# throughhole_xbee.net
KiCad netlist of a schematic drawn in EAGLE
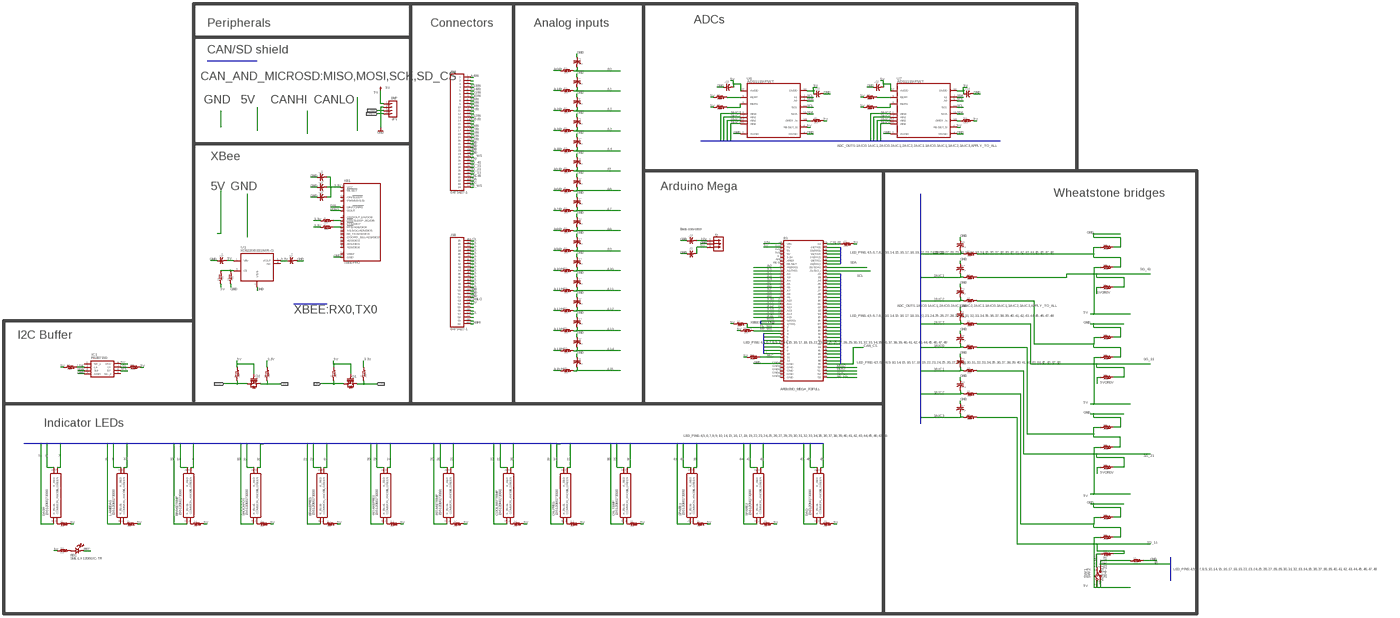
[diagram p0: schematic, sheet 1, overview]
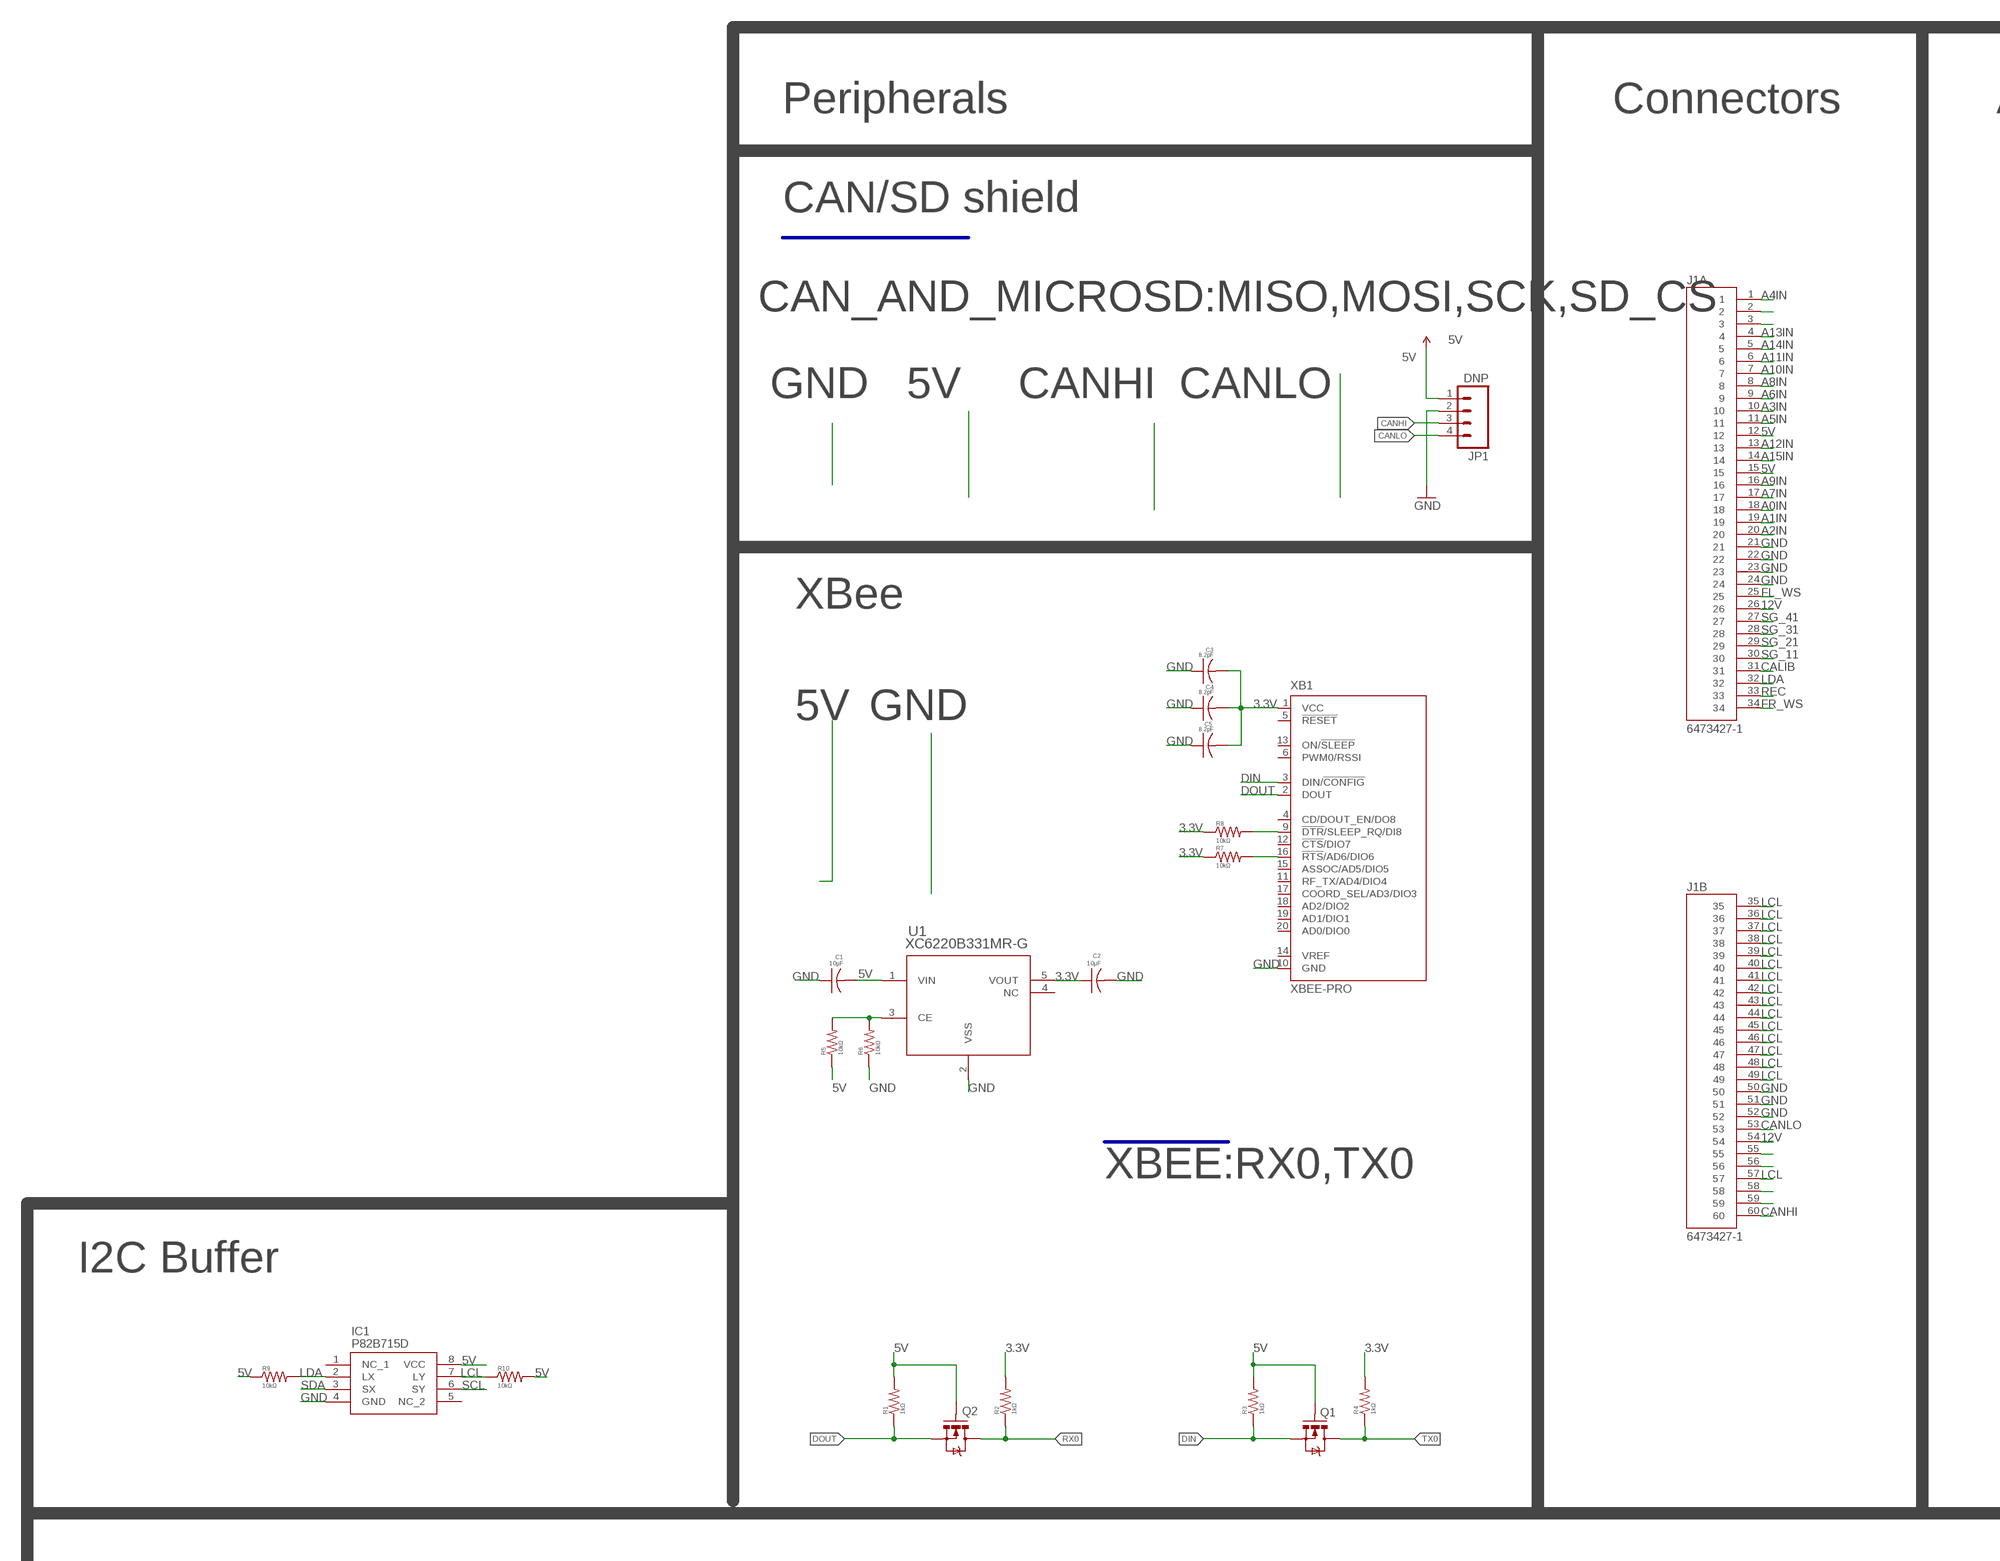
[diagram p1: schematic, sheet 1, part 1 of 5]
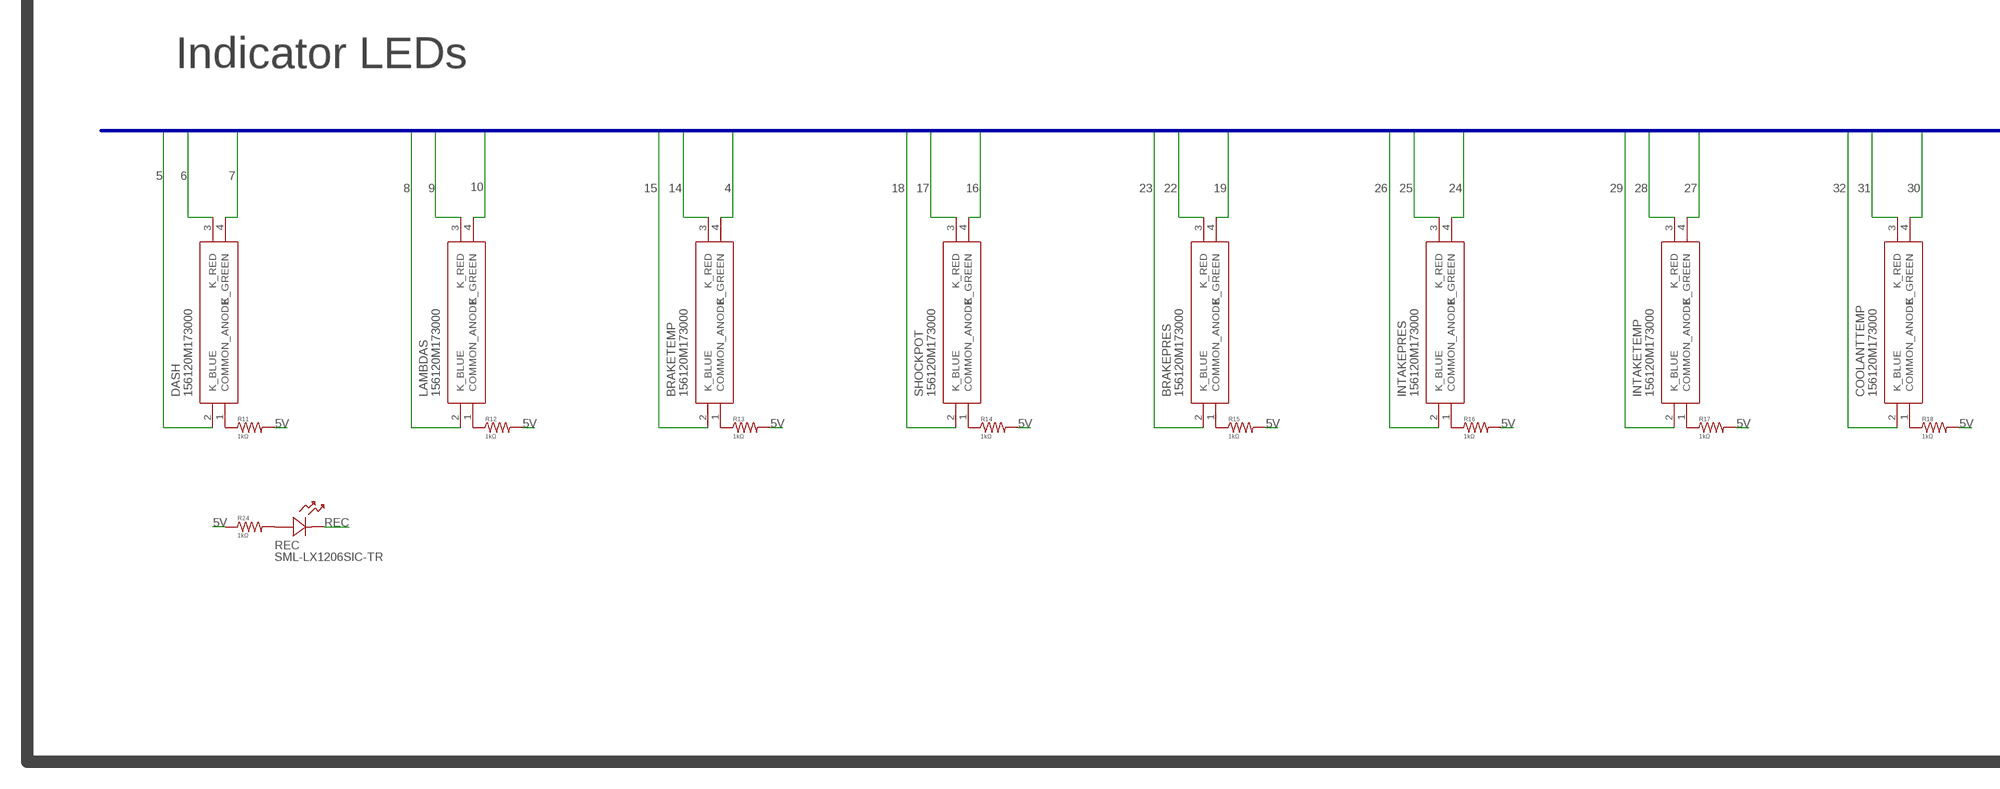
[diagram p2: schematic, sheet 1, part 2 of 5]
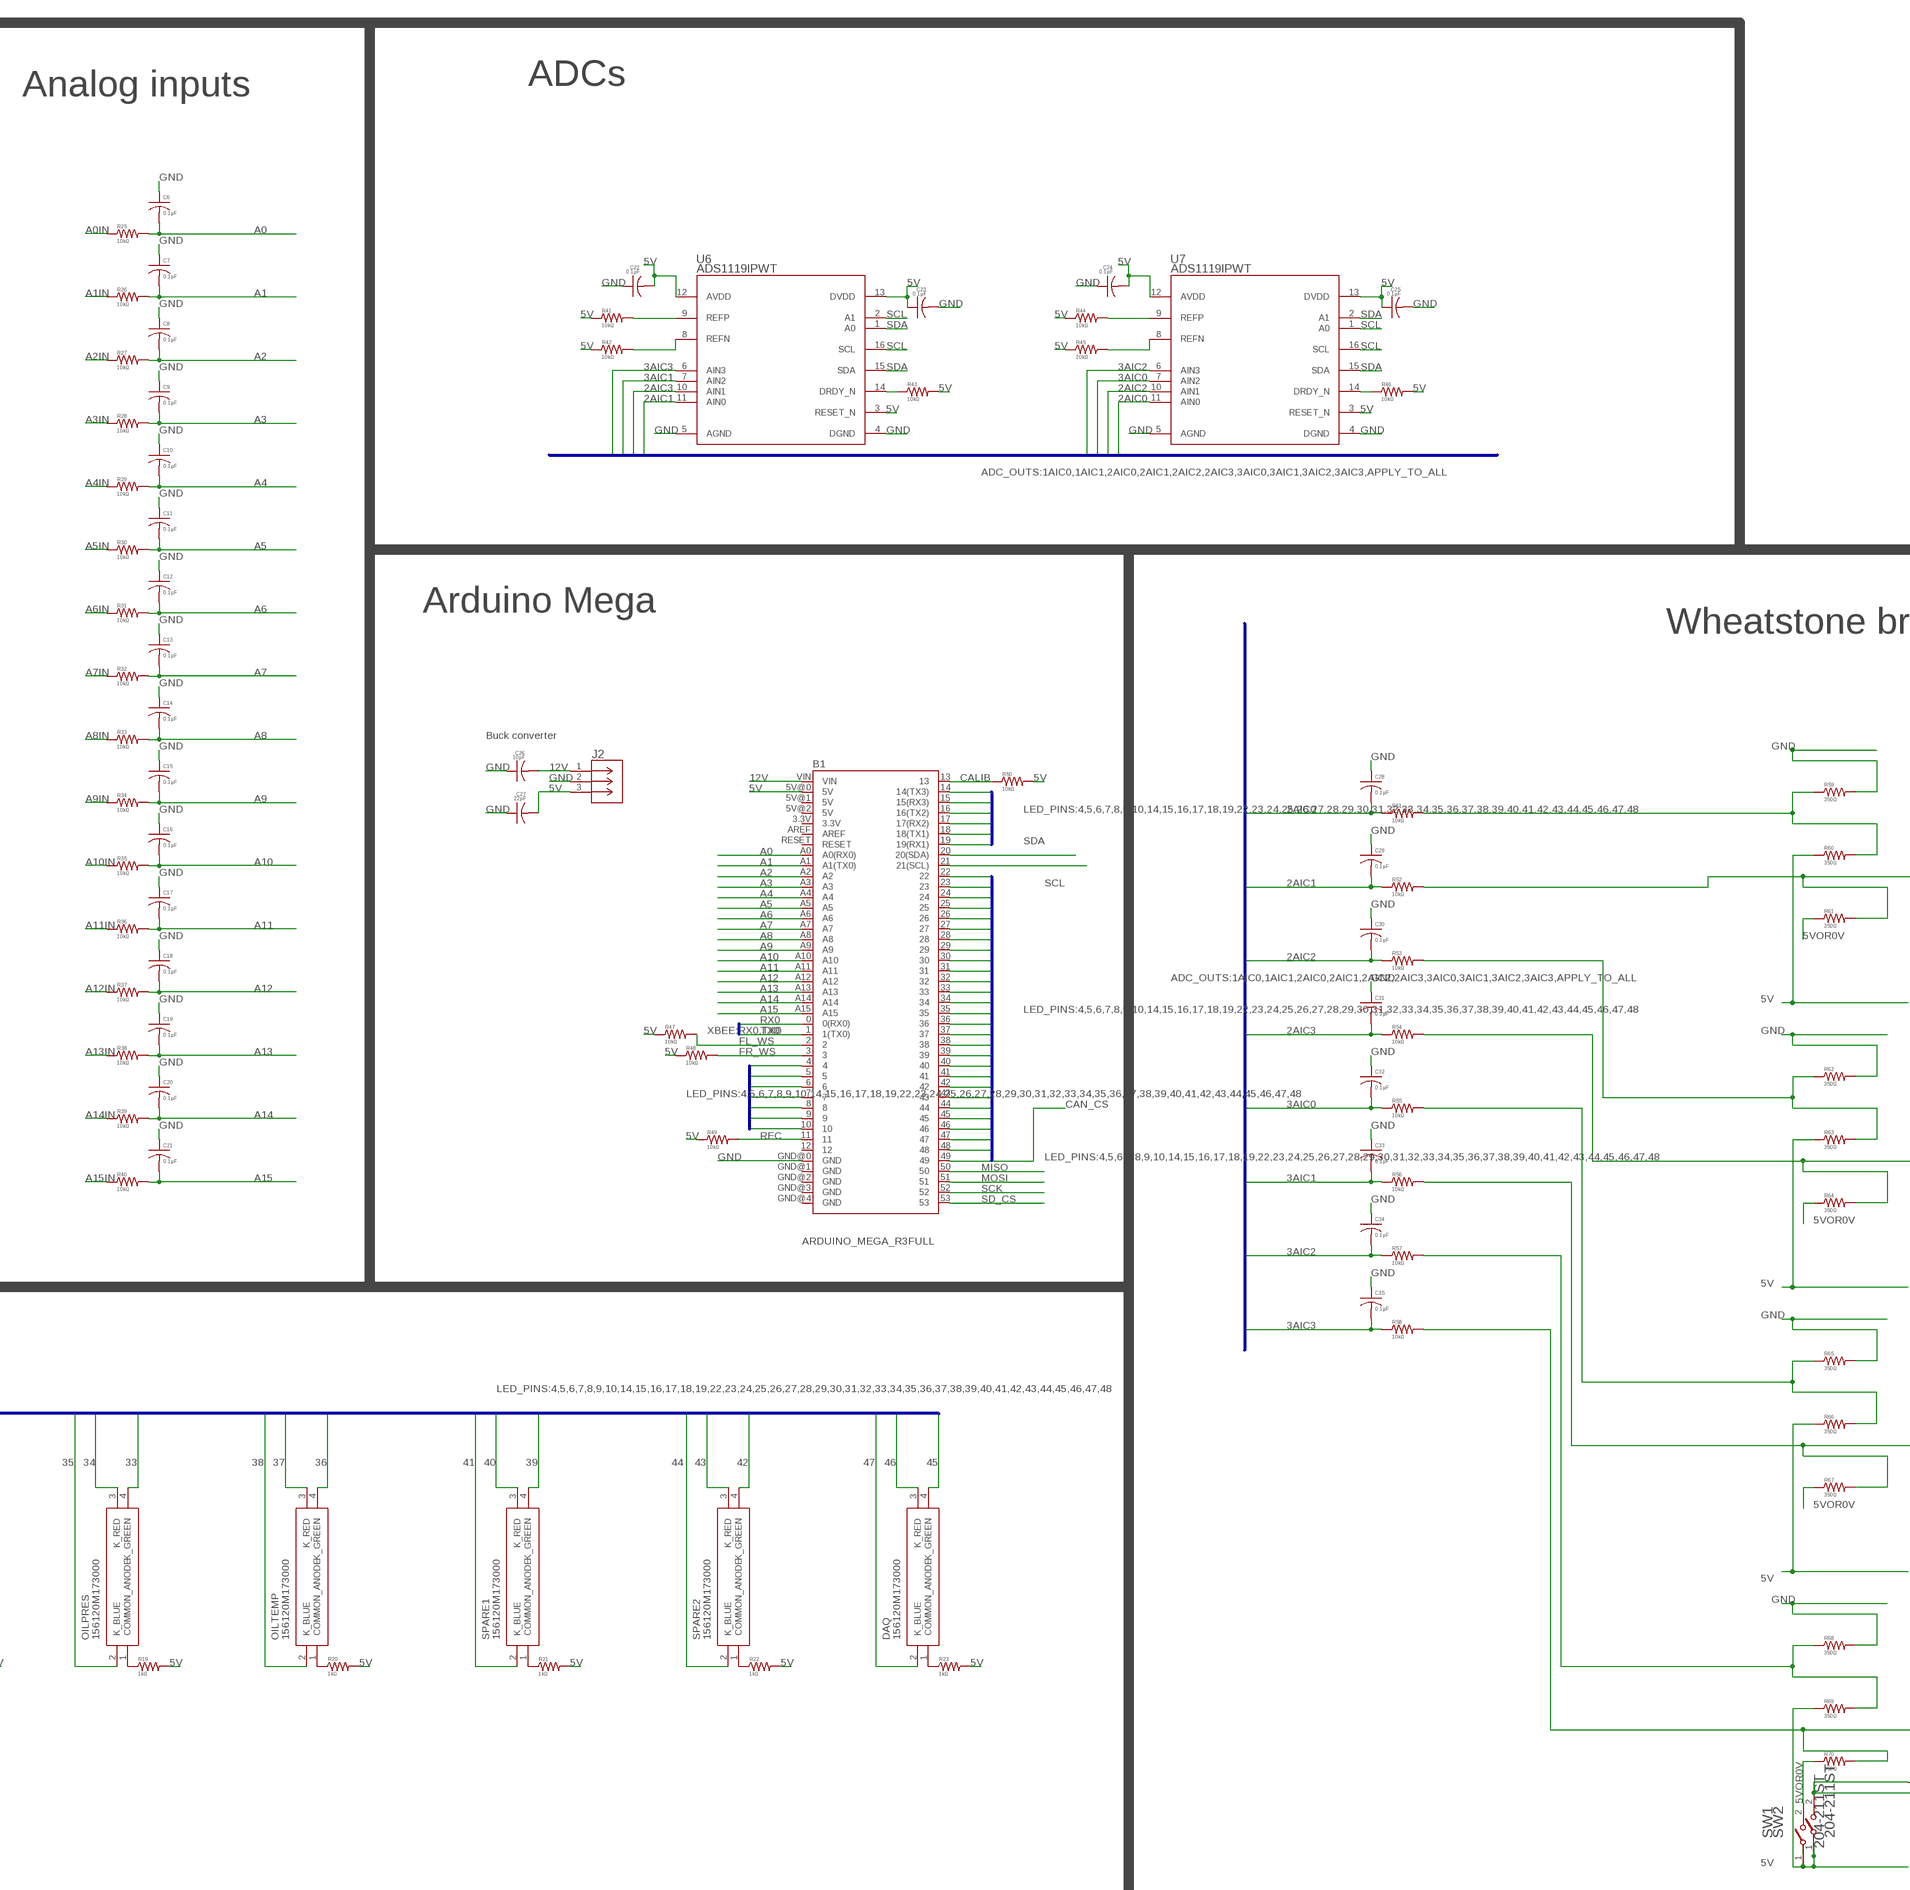
[diagram p3: schematic, sheet 1, part 3 of 5]
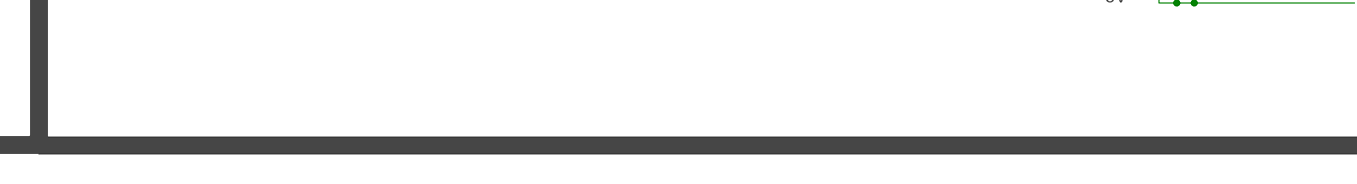
[diagram p4: schematic, sheet 1, part 4 of 5]
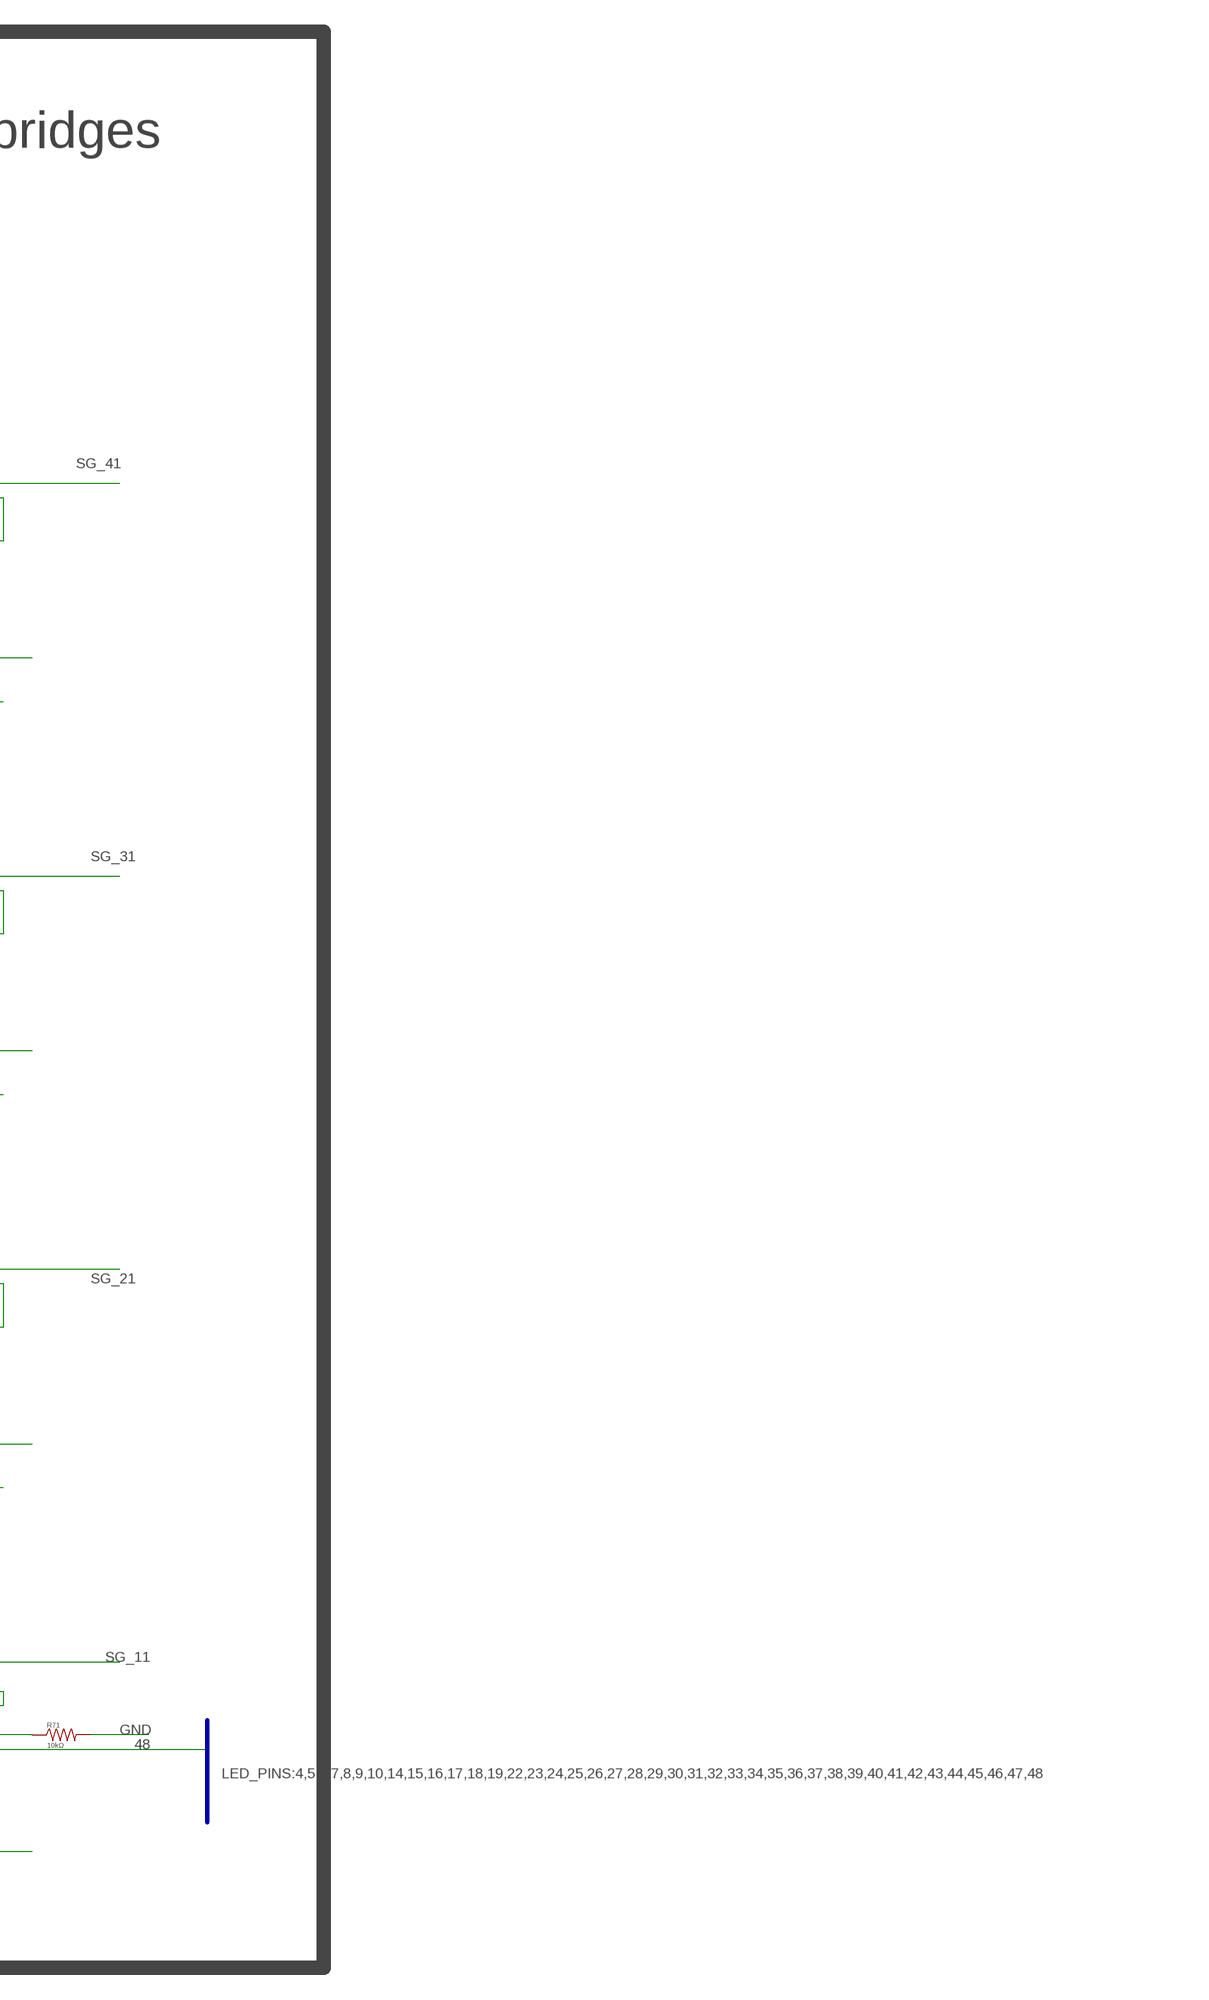
[diagram p5: schematic, sheet 1, part 5 of 5]
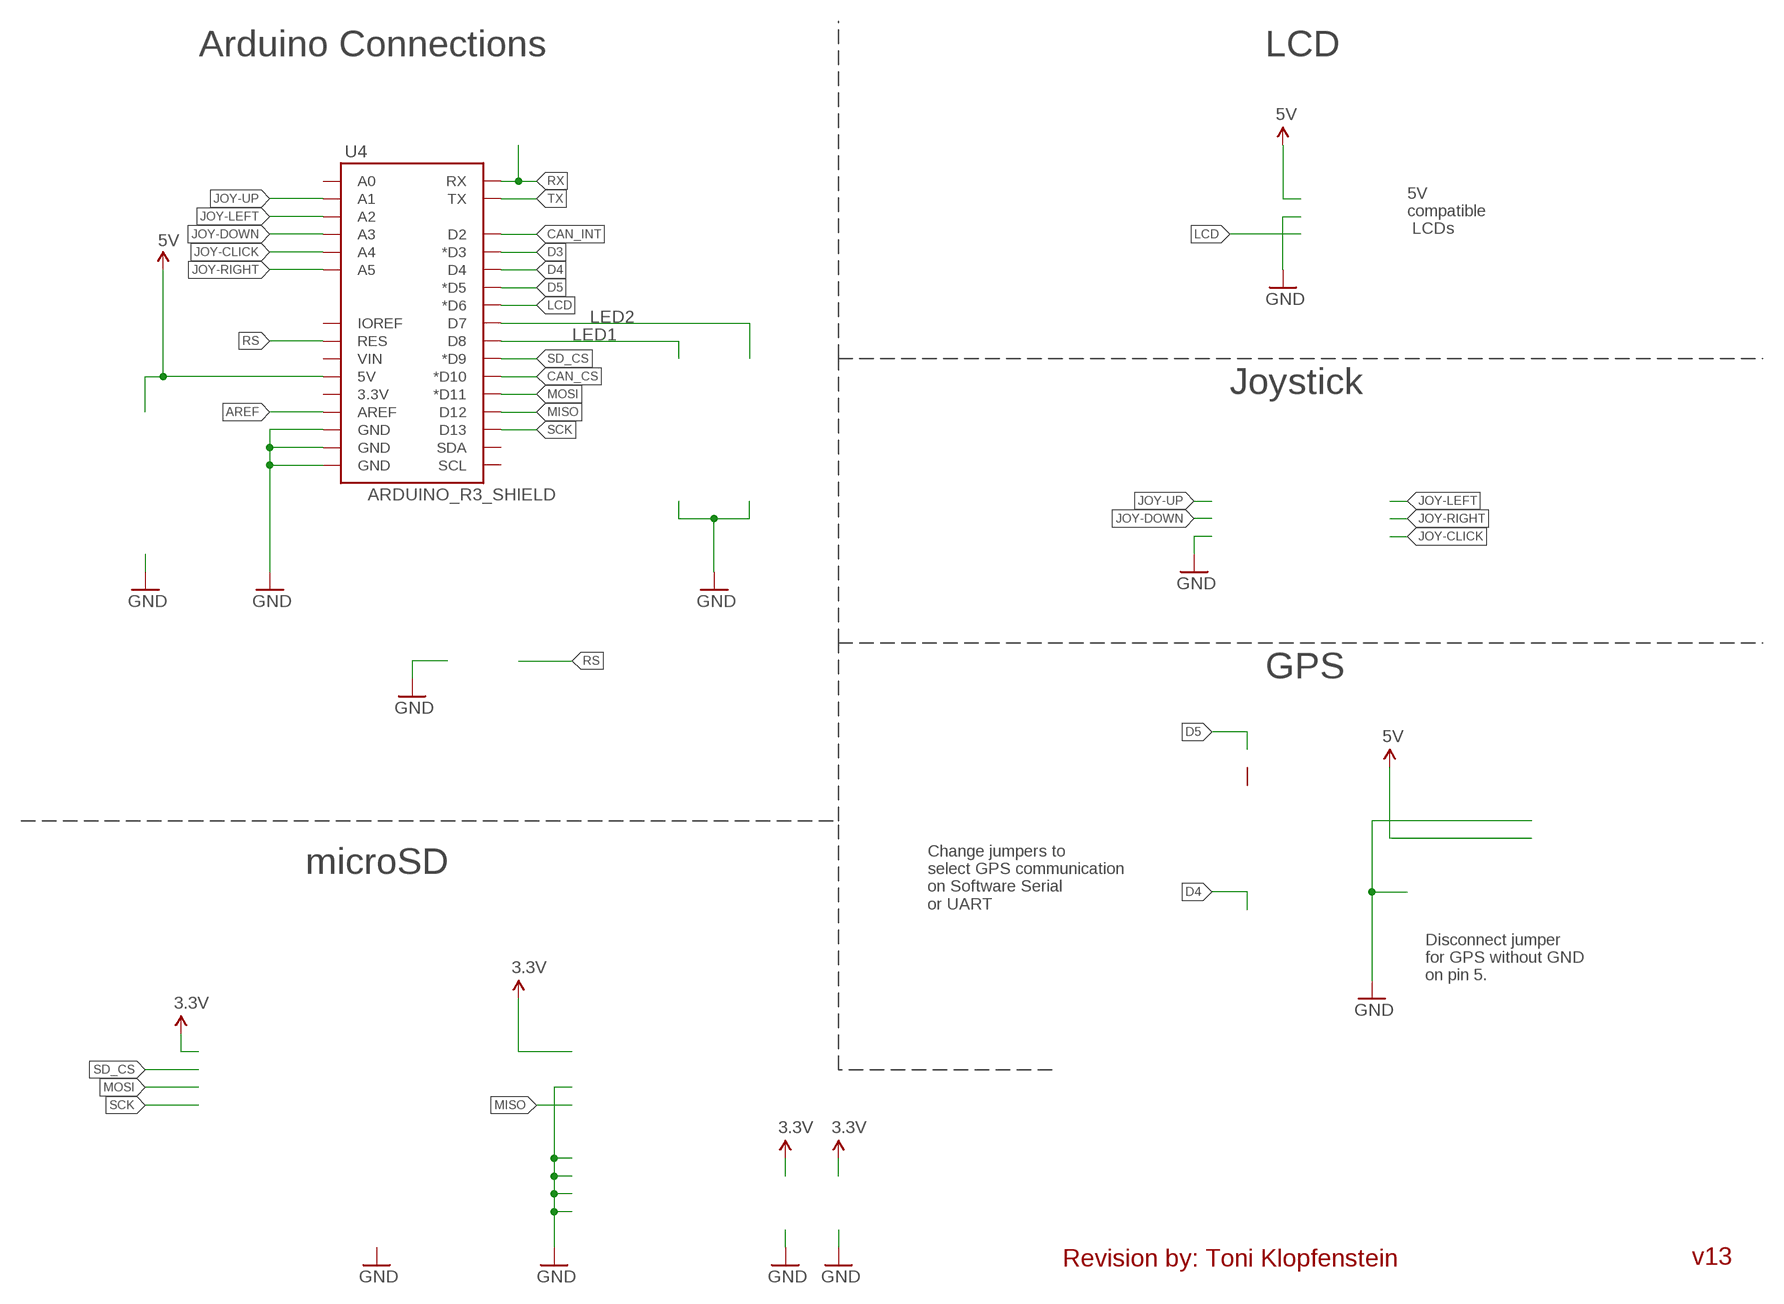
[diagram p6: schematic, sheet 2]

(export (version "E")
  (design (tool "Eeschema 10.0.6"))
  (components
    (comp (ref "B1")
      (value "ARDUINO_MEGA_R3FULL")
      (footprint "eagle-import:ARDUINO_MEGA")
      (libsource (lib "eagle-import") (part "ARDUINO_MEGA_R3FULL"))
    )
    (comp (ref "BRAKEPRES")
      (value "156120M173000")
      (footprint "eagle-import:156120M173000")
      (fields (field (name "MOUSER_PART_NUMBER") "710-156120M173000"))
      (libsource (lib "eagle-import") (part "156120M173000"))
    )
    (comp (ref "BRAKETEMP")
      (value "156120M173000")
      (footprint "eagle-import:156120M173000")
      (fields (field (name "MOUSER_PART_NUMBER") "710-156120M173000"))
      (libsource (lib "eagle-import") (part "156120M173000"))
    )
    (comp (ref "C1")
      (value "10μF")
      (footprint "eagle-import:C1206")
      (libsource (lib "eagle-import") (part "C-USC1206"))
    )
    (comp (ref "C2")
      (value "10μF")
      (footprint "eagle-import:C1206")
      (libsource (lib "eagle-import") (part "C-USC1206"))
    )
    (comp (ref "C3")
      (value "8.2pF")
      (footprint "eagle-import:C1206")
      (libsource (lib "eagle-import") (part "C-USC1206"))
    )
    (comp (ref "C4")
      (value "8.2pF")
      (footprint "eagle-import:C1206")
      (libsource (lib "eagle-import") (part "C-USC1206"))
    )
    (comp (ref "C5")
      (value "8.2pF")
      (footprint "eagle-import:C1206")
      (libsource (lib "eagle-import") (part "C-USC1206"))
    )
    (comp (ref "C6")
      (value "0.1μF")
      (footprint "eagle-import:C1206")
      (libsource (lib "eagle-import") (part "C-USC1206"))
    )
    (comp (ref "C7")
      (value "0.1μF")
      (footprint "eagle-import:C1206")
      (libsource (lib "eagle-import") (part "C-USC1206"))
    )
    (comp (ref "C8")
      (value "0.1μF")
      (footprint "eagle-import:C1206")
      (libsource (lib "eagle-import") (part "C-USC1206"))
    )
    (comp (ref "C9")
      (value "0.1μF")
      (footprint "eagle-import:C1206")
      (libsource (lib "eagle-import") (part "C-USC1206"))
    )
    (comp (ref "C10")
      (value "0.1μF")
      (footprint "eagle-import:C1206")
      (libsource (lib "eagle-import") (part "C-USC1206"))
    )
    (comp (ref "C11")
      (value "0.1μF")
      (footprint "eagle-import:C1206")
      (libsource (lib "eagle-import") (part "C-USC1206"))
    )
    (comp (ref "C12")
      (value "0.1μF")
      (footprint "eagle-import:C1206")
      (libsource (lib "eagle-import") (part "C-USC1206"))
    )
    (comp (ref "C13")
      (value "0.1μF")
      (footprint "eagle-import:C1206")
      (libsource (lib "eagle-import") (part "C-USC1206"))
    )
    (comp (ref "C14")
      (value "0.1μF")
      (footprint "eagle-import:C1206")
      (libsource (lib "eagle-import") (part "C-USC1206"))
    )
    (comp (ref "C15")
      (value "0.1μF")
      (footprint "eagle-import:C1206")
      (libsource (lib "eagle-import") (part "C-USC1206"))
    )
    (comp (ref "C16")
      (value "0.1μF")
      (footprint "eagle-import:C1206")
      (libsource (lib "eagle-import") (part "C-USC1206"))
    )
    (comp (ref "C17")
      (value "0.1μF")
      (footprint "eagle-import:C1206")
      (libsource (lib "eagle-import") (part "C-USC1206"))
    )
    (comp (ref "C18")
      (value "0.1μF")
      (footprint "eagle-import:C1206")
      (libsource (lib "eagle-import") (part "C-USC1206"))
    )
    (comp (ref "C19")
      (value "0.1μF")
      (footprint "eagle-import:C1206")
      (libsource (lib "eagle-import") (part "C-USC1206"))
    )
    (comp (ref "C20")
      (value "0.1μF")
      (footprint "eagle-import:C1206")
      (libsource (lib "eagle-import") (part "C-USC1206"))
    )
    (comp (ref "C21")
      (value "0.1μF")
      (footprint "eagle-import:C1206")
      (libsource (lib "eagle-import") (part "C-USC1206"))
    )
    (comp (ref "C22")
      (value "0.1μF")
      (footprint "eagle-import:C1206")
      (libsource (lib "eagle-import") (part "C-USC1206"))
    )
    (comp (ref "C23")
      (value "0.1μF")
      (footprint "eagle-import:C1206")
      (libsource (lib "eagle-import") (part "C-USC1206"))
    )
    (comp (ref "C24")
      (value "0.1μF")
      (footprint "eagle-import:C1206")
      (libsource (lib "eagle-import") (part "C-USC1206"))
    )
    (comp (ref "C25")
      (value "0.1μF")
      (footprint "eagle-import:C1206")
      (libsource (lib "eagle-import") (part "C-USC1206"))
    )
    (comp (ref "C26")
      (value "10μF")
      (footprint "eagle-import:C1206")
      (libsource (lib "eagle-import") (part "C-USC1206"))
    )
    (comp (ref "C27")
      (value "22μF")
      (footprint "eagle-import:C1206")
      (libsource (lib "eagle-import") (part "C-USC1206"))
    )
    (comp (ref "C28")
      (value "0.1μF")
      (footprint "eagle-import:C1206")
      (libsource (lib "eagle-import") (part "C-USC1206"))
    )
    (comp (ref "C29")
      (value "0.1μF")
      (footprint "eagle-import:C1206")
      (libsource (lib "eagle-import") (part "C-USC1206"))
    )
    (comp (ref "C30")
      (value "0.1μF")
      (footprint "eagle-import:C1206")
      (libsource (lib "eagle-import") (part "C-USC1206"))
    )
    (comp (ref "C31")
      (value "0.1μF")
      (footprint "eagle-import:C1206")
      (libsource (lib "eagle-import") (part "C-USC1206"))
    )
    (comp (ref "C32")
      (value "0.1μF")
      (footprint "eagle-import:C1206")
      (libsource (lib "eagle-import") (part "C-USC1206"))
    )
    (comp (ref "C33")
      (value "0.1μF")
      (footprint "eagle-import:C1206")
      (libsource (lib "eagle-import") (part "C-USC1206"))
    )
    (comp (ref "C34")
      (value "0.1μF")
      (footprint "eagle-import:C1206")
      (libsource (lib "eagle-import") (part "C-USC1206"))
    )
    (comp (ref "C35")
      (value "0.1μF")
      (footprint "eagle-import:C1206")
      (libsource (lib "eagle-import") (part "C-USC1206"))
    )
    (comp (ref "COOLANTTEMP")
      (value "156120M173000")
      (footprint "eagle-import:156120M173000")
      (fields (field (name "MOUSER_PART_NUMBER") "710-156120M173000"))
      (libsource (lib "eagle-import") (part "156120M173000"))
    )
    (comp (ref "DAQ")
      (value "156120M173000")
      (footprint "eagle-import:156120M173000")
      (fields (field (name "MOUSER_PART_NUMBER") "710-156120M173000"))
      (libsource (lib "eagle-import") (part "156120M173000"))
    )
    (comp (ref "DASH")
      (value "156120M173000")
      (footprint "eagle-import:156120M173000")
      (fields (field (name "MOUSER_PART_NUMBER") "710-156120M173000"))
      (libsource (lib "eagle-import") (part "156120M173000"))
    )
    (comp (ref "IC1")
      (value "P82B715D")
      (footprint "eagle-import:SOIC127P600X175-8N")
      (fields (field (name "MOUSER_PART_NUMBER") "595-P82B715D"))
      (libsource (lib "eagle-import") (part "P82B715D"))
    )
    (comp (ref "INTAKEPRES")
      (value "156120M173000")
      (footprint "eagle-import:156120M173000")
      (fields (field (name "MOUSER_PART_NUMBER") "710-156120M173000"))
      (libsource (lib "eagle-import") (part "156120M173000"))
    )
    (comp (ref "INTAKETEMP")
      (value "156120M173000")
      (footprint "eagle-import:156120M173000")
      (fields (field (name "MOUSER_PART_NUMBER") "710-156120M173000"))
      (libsource (lib "eagle-import") (part "156120M173000"))
    )
    (comp (ref "J1")
      (value "6473427-1")
      (footprint "eagle-import:TE_6473427-1")
      (fields (field (name "MF") "TE Connectivity"))
      (libsource (lib "eagle-import") (part "6473427-1"))
    )
    (comp (ref "J2")
      (value "VR10S05")
      (footprint "eagle-import:CONN3_10S05_XPP")
      (fields (field (name "COPYRIGHT") "Copyright (C) 2022 Ultra Librarian. All rights reserved."))
      (libsource (lib "eagle-import") (part "VR10S05"))
    )
    (comp (ref "JP1")
      (value "DNP")
      (footprint "eagle-import:1X04")
      (libsource (lib "eagle-import") (part "M04PTH"))
    )
    (comp (ref "LAMBDAS")
      (value "156120M173000")
      (footprint "eagle-import:156120M173000")
      (fields (field (name "MOUSER_PART_NUMBER") "710-156120M173000"))
      (libsource (lib "eagle-import") (part "156120M173000"))
    )
    (comp (ref "OILPRES")
      (value "156120M173000")
      (footprint "eagle-import:156120M173000")
      (fields (field (name "MOUSER_PART_NUMBER") "710-156120M173000"))
      (libsource (lib "eagle-import") (part "156120M173000"))
    )
    (comp (ref "OILTEMP")
      (value "156120M173000")
      (footprint "eagle-import:156120M173000")
      (fields (field (name "MOUSER_PART_NUMBER") "710-156120M173000"))
      (libsource (lib "eagle-import") (part "156120M173000"))
    )
    (comp (ref "Q1")
      (value "MOSFET-NCHANNELSMD")
      (footprint "eagle-import:SOT23-3")
      (libsource (lib "eagle-import") (part "MOSFET-NCHANNELSMD"))
    )
    (comp (ref "Q2")
      (value "MOSFET-NCHANNELSMD")
      (footprint "eagle-import:SOT23-3")
      (libsource (lib "eagle-import") (part "MOSFET-NCHANNELSMD"))
    )
    (comp (ref "R1")
      (value "1kΩ")
      (footprint "eagle-import:R1206")
      (libsource (lib "eagle-import") (part "R-US_R1206"))
    )
    (comp (ref "R2")
      (value "1kΩ")
      (footprint "eagle-import:R1206")
      (libsource (lib "eagle-import") (part "R-US_R1206"))
    )
    (comp (ref "R3")
      (value "1kΩ")
      (footprint "eagle-import:R1206")
      (libsource (lib "eagle-import") (part "R-US_R1206"))
    )
    (comp (ref "R4")
      (value "1kΩ")
      (footprint "eagle-import:R1206")
      (libsource (lib "eagle-import") (part "R-US_R1206"))
    )
    (comp (ref "R5")
      (value "10kΩ")
      (footprint "eagle-import:R1206")
      (libsource (lib "eagle-import") (part "R-US_R1206"))
    )
    (comp (ref "R6")
      (value "10kΩ")
      (footprint "eagle-import:R1206")
      (libsource (lib "eagle-import") (part "R-US_R1206"))
    )
    (comp (ref "R7")
      (value "10kΩ")
      (footprint "eagle-import:R1206")
      (libsource (lib "eagle-import") (part "R-US_R1206"))
    )
    (comp (ref "R8")
      (value "10kΩ")
      (footprint "eagle-import:R1206")
      (libsource (lib "eagle-import") (part "R-US_R1206"))
    )
    (comp (ref "R9")
      (value "10kΩ")
      (footprint "eagle-import:R1206")
      (libsource (lib "eagle-import") (part "R-US_R1206"))
    )
    (comp (ref "R10")
      (value "10kΩ")
      (footprint "eagle-import:R1206")
      (libsource (lib "eagle-import") (part "R-US_R1206"))
    )
    (comp (ref "R11")
      (value "1kΩ")
      (footprint "eagle-import:R1206")
      (libsource (lib "eagle-import") (part "R-US_R1206"))
    )
    (comp (ref "R12")
      (value "1kΩ")
      (footprint "eagle-import:R1206")
      (libsource (lib "eagle-import") (part "R-US_R1206"))
    )
    (comp (ref "R13")
      (value "1kΩ")
      (footprint "eagle-import:R1206")
      (libsource (lib "eagle-import") (part "R-US_R1206"))
    )
    (comp (ref "R14")
      (value "1kΩ")
      (footprint "eagle-import:R1206")
      (libsource (lib "eagle-import") (part "R-US_R1206"))
    )
    (comp (ref "R15")
      (value "1kΩ")
      (footprint "eagle-import:R1206")
      (libsource (lib "eagle-import") (part "R-US_R1206"))
    )
    (comp (ref "R16")
      (value "1kΩ")
      (footprint "eagle-import:R1206")
      (libsource (lib "eagle-import") (part "R-US_R1206"))
    )
    (comp (ref "R17")
      (value "1kΩ")
      (footprint "eagle-import:R1206")
      (libsource (lib "eagle-import") (part "R-US_R1206"))
    )
    (comp (ref "R18")
      (value "1kΩ")
      (footprint "eagle-import:R1206")
      (libsource (lib "eagle-import") (part "R-US_R1206"))
    )
    (comp (ref "R19")
      (value "1kΩ")
      (footprint "eagle-import:R1206")
      (libsource (lib "eagle-import") (part "R-US_R1206"))
    )
    (comp (ref "R20")
      (value "1kΩ")
      (footprint "eagle-import:R1206")
      (libsource (lib "eagle-import") (part "R-US_R1206"))
    )
    (comp (ref "R21")
      (value "1kΩ")
      (footprint "eagle-import:R1206")
      (libsource (lib "eagle-import") (part "R-US_R1206"))
    )
    (comp (ref "R22")
      (value "1kΩ")
      (footprint "eagle-import:R1206")
      (libsource (lib "eagle-import") (part "R-US_R1206"))
    )
    (comp (ref "R23")
      (value "1kΩ")
      (footprint "eagle-import:R1206")
      (libsource (lib "eagle-import") (part "R-US_R1206"))
    )
    (comp (ref "R24")
      (value "1kΩ")
      (footprint "eagle-import:R1206")
      (libsource (lib "eagle-import") (part "R-US_R1206"))
    )
    (comp (ref "R25")
      (value "10kΩ")
      (footprint "eagle-import:R1206")
      (libsource (lib "eagle-import") (part "R-US_R1206"))
    )
    (comp (ref "R26")
      (value "10kΩ")
      (footprint "eagle-import:R1206")
      (libsource (lib "eagle-import") (part "R-US_R1206"))
    )
    (comp (ref "R27")
      (value "10kΩ")
      (footprint "eagle-import:R1206")
      (libsource (lib "eagle-import") (part "R-US_R1206"))
    )
    (comp (ref "R28")
      (value "10kΩ")
      (footprint "eagle-import:R1206")
      (libsource (lib "eagle-import") (part "R-US_R1206"))
    )
    (comp (ref "R29")
      (value "10kΩ")
      (footprint "eagle-import:R1206")
      (libsource (lib "eagle-import") (part "R-US_R1206"))
    )
    (comp (ref "R30")
      (value "10kΩ")
      (footprint "eagle-import:R1206")
      (libsource (lib "eagle-import") (part "R-US_R1206"))
    )
    (comp (ref "R31")
      (value "10kΩ")
      (footprint "eagle-import:R1206")
      (libsource (lib "eagle-import") (part "R-US_R1206"))
    )
    (comp (ref "R32")
      (value "10kΩ")
      (footprint "eagle-import:R1206")
      (libsource (lib "eagle-import") (part "R-US_R1206"))
    )
    (comp (ref "R33")
      (value "10kΩ")
      (footprint "eagle-import:R1206")
      (libsource (lib "eagle-import") (part "R-US_R1206"))
    )
    (comp (ref "R34")
      (value "10kΩ")
      (footprint "eagle-import:R1206")
      (libsource (lib "eagle-import") (part "R-US_R1206"))
    )
    (comp (ref "R35")
      (value "10kΩ")
      (footprint "eagle-import:R1206")
      (libsource (lib "eagle-import") (part "R-US_R1206"))
    )
    (comp (ref "R36")
      (value "10kΩ")
      (footprint "eagle-import:R1206")
      (libsource (lib "eagle-import") (part "R-US_R1206"))
    )
    (comp (ref "R37")
      (value "10kΩ")
      (footprint "eagle-import:R1206")
      (libsource (lib "eagle-import") (part "R-US_R1206"))
    )
    (comp (ref "R38")
      (value "10kΩ")
      (footprint "eagle-import:R1206")
      (libsource (lib "eagle-import") (part "R-US_R1206"))
    )
    (comp (ref "R39")
      (value "10kΩ")
      (footprint "eagle-import:R1206")
      (libsource (lib "eagle-import") (part "R-US_R1206"))
    )
    (comp (ref "R40")
      (value "10kΩ")
      (footprint "eagle-import:R1206")
      (libsource (lib "eagle-import") (part "R-US_R1206"))
    )
    (comp (ref "R41")
      (value "10kΩ")
      (footprint "eagle-import:R1206")
      (libsource (lib "eagle-import") (part "R-US_R1206"))
    )
    (comp (ref "R42")
      (value "10kΩ")
      (footprint "eagle-import:R1206")
      (libsource (lib "eagle-import") (part "R-US_R1206"))
    )
    (comp (ref "R43")
      (value "10kΩ")
      (footprint "eagle-import:R1206")
      (libsource (lib "eagle-import") (part "R-US_R1206"))
    )
    (comp (ref "R44")
      (value "10kΩ")
      (footprint "eagle-import:R1206")
      (libsource (lib "eagle-import") (part "R-US_R1206"))
    )
    (comp (ref "R45")
      (value "10kΩ")
      (footprint "eagle-import:R1206")
      (libsource (lib "eagle-import") (part "R-US_R1206"))
    )
    (comp (ref "R46")
      (value "10kΩ")
      (footprint "eagle-import:R1206")
      (libsource (lib "eagle-import") (part "R-US_R1206"))
    )
    (comp (ref "R47")
      (value "10kΩ")
      (footprint "eagle-import:R1206")
      (libsource (lib "eagle-import") (part "R-US_R1206"))
    )
    (comp (ref "R48")
      (value "10kΩ")
      (footprint "eagle-import:R1206")
      (libsource (lib "eagle-import") (part "R-US_R1206"))
    )
    (comp (ref "R49")
      (value "10kΩ")
      (footprint "eagle-import:R1206")
      (libsource (lib "eagle-import") (part "R-US_R1206"))
    )
    (comp (ref "R50")
      (value "10kΩ")
      (footprint "eagle-import:R1206")
      (libsource (lib "eagle-import") (part "R-US_R1206"))
    )
    (comp (ref "R51")
      (value "10kΩ")
      (footprint "eagle-import:R1206")
      (libsource (lib "eagle-import") (part "R-US_R1206"))
    )
    (comp (ref "R52")
      (value "10kΩ")
      (footprint "eagle-import:R1206")
      (libsource (lib "eagle-import") (part "R-US_R1206"))
    )
    (comp (ref "R53")
      (value "10kΩ")
      (footprint "eagle-import:R1206")
      (libsource (lib "eagle-import") (part "R-US_R1206"))
    )
    (comp (ref "R54")
      (value "10kΩ")
      (footprint "eagle-import:R1206")
      (libsource (lib "eagle-import") (part "R-US_R1206"))
    )
    (comp (ref "R55")
      (value "10kΩ")
      (footprint "eagle-import:R1206")
      (libsource (lib "eagle-import") (part "R-US_R1206"))
    )
    (comp (ref "R56")
      (value "10kΩ")
      (footprint "eagle-import:R1206")
      (libsource (lib "eagle-import") (part "R-US_R1206"))
    )
    (comp (ref "R57")
      (value "10kΩ")
      (footprint "eagle-import:R1206")
      (libsource (lib "eagle-import") (part "R-US_R1206"))
    )
    (comp (ref "R58")
      (value "10kΩ")
      (footprint "eagle-import:R1206")
      (libsource (lib "eagle-import") (part "R-US_R1206"))
    )
    (comp (ref "R59")
      (value "350Ω")
      (footprint "eagle-import:R1206")
      (libsource (lib "eagle-import") (part "R-US_R1206"))
    )
    (comp (ref "R60")
      (value "350Ω")
      (footprint "eagle-import:R1206")
      (libsource (lib "eagle-import") (part "R-US_R1206"))
    )
    (comp (ref "R61")
      (value "350Ω")
      (footprint "eagle-import:R1206")
      (libsource (lib "eagle-import") (part "R-US_R1206"))
    )
    (comp (ref "R62")
      (value "350Ω")
      (footprint "eagle-import:R1206")
      (libsource (lib "eagle-import") (part "R-US_R1206"))
    )
    (comp (ref "R63")
      (value "350Ω")
      (footprint "eagle-import:R1206")
      (libsource (lib "eagle-import") (part "R-US_R1206"))
    )
    (comp (ref "R64")
      (value "350Ω")
      (footprint "eagle-import:R1206")
      (libsource (lib "eagle-import") (part "R-US_R1206"))
    )
    (comp (ref "R65")
      (value "350Ω")
      (footprint "eagle-import:R1206")
      (libsource (lib "eagle-import") (part "R-US_R1206"))
    )
    (comp (ref "R66")
      (value "350Ω")
      (footprint "eagle-import:R1206")
      (libsource (lib "eagle-import") (part "R-US_R1206"))
    )
    (comp (ref "R67")
      (value "350Ω")
      (footprint "eagle-import:R1206")
      (libsource (lib "eagle-import") (part "R-US_R1206"))
    )
    (comp (ref "R68")
      (value "350Ω")
      (footprint "eagle-import:R1206")
      (libsource (lib "eagle-import") (part "R-US_R1206"))
    )
    (comp (ref "R69")
      (value "350Ω")
      (footprint "eagle-import:R1206")
      (libsource (lib "eagle-import") (part "R-US_R1206"))
    )
    (comp (ref "R70")
      (value "350Ω")
      (footprint "eagle-import:R1206")
      (libsource (lib "eagle-import") (part "R-US_R1206"))
    )
    (comp (ref "R71")
      (value "10kΩ")
      (footprint "eagle-import:R1206")
      (libsource (lib "eagle-import") (part "R-US_R1206"))
    )
    (comp (ref "REC")
      (value "SML-LX1206SIC-TR")
      (footprint "eagle-import:LED_SML-LX1206SIC-TR_LUM")
      (fields (field (name "COPYRIGHT") "Copyright (C) 2021 Ultra Librarian. All rights reserved."))
      (libsource (lib "eagle-import") (part "SML-LX1206SIC-TR"))
    )
    (comp (ref "SHOCKPOT")
      (value "156120M173000")
      (footprint "eagle-import:156120M173000")
      (fields (field (name "MOUSER_PART_NUMBER") "710-156120M173000"))
      (libsource (lib "eagle-import") (part "156120M173000"))
    )
    (comp (ref "SPARE1")
      (value "156120M173000")
      (footprint "eagle-import:156120M173000")
      (fields (field (name "MOUSER_PART_NUMBER") "710-156120M173000"))
      (libsource (lib "eagle-import") (part "156120M173000"))
    )
    (comp (ref "SPARE2")
      (value "156120M173000")
      (footprint "eagle-import:156120M173000")
      (fields (field (name "MOUSER_PART_NUMBER") "710-156120M173000"))
      (libsource (lib "eagle-import") (part "156120M173000"))
    )
    (comp (ref "SW1")
      (value "CTS_ELECTROCOMPONENTS_204-211STCTS_ELECTROCOMPONENTS_204-211ST_0_0")
      (footprint "eagle-import:CTS_ELECTROCOMPONENTS_204-211ST_0")
      (fields
        (field (name "DIGIKEY_PART_NUMBER") "CT3103CT-ND")
        (field (name "MF") "CTS Electrocomponents")
        (field (name "MOUSER_PART_NUMBER") "774-204-211STR")
      )
      (libsource (lib "eagle-import") (part "CTS_ELECTROCOMPONENTS_204-211STCTS_ELECTROCOMPONENTS_204-211ST_0_0"))
    )
    (comp (ref "SW2")
      (value "CTS_ELECTROCOMPONENTS_204-211STCTS_ELECTROCOMPONENTS_204-211ST_0_0")
      (footprint "eagle-import:CTS_ELECTROCOMPONENTS_204-211ST_0")
      (fields
        (field (name "DIGIKEY_PART_NUMBER") "CT3103CT-ND")
        (field (name "MF") "CTS Electrocomponents")
        (field (name "MOUSER_PART_NUMBER") "774-204-211STR")
      )
      (libsource (lib "eagle-import") (part "CTS_ELECTROCOMPONENTS_204-211STCTS_ELECTROCOMPONENTS_204-211ST_0_0"))
    )
    (comp (ref "U1")
      (value "XC6220B331MR-G")
      (footprint "eagle-import:SOT-25_TOR")
      (fields (field (name "COPYRIGHT") "Copyright (C) 2022 Ultra Librarian. All rights reserved."))
      (libsource (lib "eagle-import") (part "XC6220B331MR-G"))
    )
    (comp (ref "U6")
      (value "ADS1119IPWT")
      (footprint "eagle-import:PW0016A_N")
      (fields (field (name "COPYRIGHT") "Copyright (C) 2021 Ultra Librarian. All rights reserved."))
      (libsource (lib "eagle-import") (part "ADS1119IPWT"))
    )
    (comp (ref "U7")
      (value "ADS1119IPWT")
      (footprint "eagle-import:PW0016A_N")
      (fields (field (name "COPYRIGHT") "Copyright (C) 2021 Ultra Librarian. All rights reserved."))
      (libsource (lib "eagle-import") (part "ADS1119IPWT"))
    )
    (comp (ref "XB1")
      (value "XBEE-PRO")
      (footprint "eagle-import:XBEE-PRO")
      (fields (field (name "MPN") "XBP24-AWI-001"))
      (libsource (lib "eagle-import") (part "XBEE-PRO"))
    )
    (comp (ref "U4")
      (value "ARDUINO_R3_SHIELD")
      (footprint "eagle-import:UNO_R3_SHIELD")
      (libsource (lib "eagle-import") (part "ARDUINO_R3_SHIELD"))
    )
  )
  (nets
    (net (code "11") (name "2AIC0") (class "Default")
      (node (ref "C28") (pin "2") (pinfunction "2_2") (pintype "passive"))
      (node (ref "R51") (pin "1") (pinfunction "1_1") (pintype "passive"))
      (node (ref "U7") (pin "11") (pinfunction "AIN0_11") (pintype "input"))
    )
    (net (code "12") (name "2AIC1") (class "Default")
      (node (ref "C29") (pin "2") (pinfunction "2_2") (pintype "passive"))
      (node (ref "R52") (pin "1") (pinfunction "1_1") (pintype "passive"))
      (node (ref "U6") (pin "11") (pinfunction "AIN0_11") (pintype "input"))
    )
    (net (code "13") (name "2AIC2") (class "Default")
      (node (ref "C30") (pin "2") (pinfunction "2_2") (pintype "passive"))
      (node (ref "R53") (pin "1") (pinfunction "1_1") (pintype "passive"))
      (node (ref "U7") (pin "10") (pinfunction "AIN1_10") (pintype "input"))
    )
    (net (code "14") (name "2AIC3") (class "Default")
      (node (ref "C31") (pin "2") (pinfunction "2_2") (pintype "passive"))
      (node (ref "R54") (pin "1") (pinfunction "1_1") (pintype "passive"))
      (node (ref "U6") (pin "10") (pinfunction "AIN1_10") (pintype "input"))
    )
    (net (code "15") (name "3.3V") (class "Default")
      (node (ref "C2") (pin "1") (pinfunction "1_1") (pintype "passive"))
      (node (ref "C3") (pin "2") (pinfunction "2_2") (pintype "passive"))
      (node (ref "C4") (pin "2") (pinfunction "2_2") (pintype "passive"))
      (node (ref "C5") (pin "2") (pinfunction "2_2") (pintype "passive"))
      (node (ref "R2") (pin "2") (pinfunction "2_2") (pintype "passive"))
      (node (ref "R4") (pin "2") (pinfunction "2_2") (pintype "passive"))
      (node (ref "R7") (pin "1") (pinfunction "1_1") (pintype "passive"))
      (node (ref "R8") (pin "1") (pinfunction "1_1") (pintype "passive"))
      (node (ref "U1") (pin "5") (pinfunction "VOUT_5") (pintype "output"))
      (node (ref "XB1") (pin "1") (pinfunction "VCC_1") (pintype "power_in"))
    )
    (net (code "16") (name "3AIC0") (class "Default")
      (node (ref "C32") (pin "2") (pinfunction "2_2") (pintype "passive"))
      (node (ref "R55") (pin "1") (pinfunction "1_1") (pintype "passive"))
      (node (ref "U7") (pin "7") (pinfunction "AIN2_7") (pintype "input"))
    )
    (net (code "17") (name "3AIC1") (class "Default")
      (node (ref "C33") (pin "2") (pinfunction "2_2") (pintype "passive"))
      (node (ref "R56") (pin "1") (pinfunction "1_1") (pintype "passive"))
      (node (ref "U6") (pin "7") (pinfunction "AIN2_7") (pintype "input"))
    )
    (net (code "18") (name "3AIC2") (class "Default")
      (node (ref "C34") (pin "2") (pinfunction "2_2") (pintype "passive"))
      (node (ref "R57") (pin "1") (pinfunction "1_1") (pintype "passive"))
      (node (ref "U7") (pin "6") (pinfunction "AIN3_6") (pintype "input"))
    )
    (net (code "19") (name "3AIC3") (class "Default")
      (node (ref "C35") (pin "2") (pinfunction "2_2") (pintype "passive"))
      (node (ref "R58") (pin "1") (pinfunction "1_1") (pintype "passive"))
      (node (ref "U6") (pin "6") (pinfunction "AIN3_6") (pintype "input"))
    )
    (net (code "20") (name "4") (class "Default")
      (node (ref "B1") (pin "4") (pinfunction "4_4") (pintype "bidirectional"))
      (node (ref "BRAKETEMP") (pin "4") (pinfunction "K_GREEN_4") (pintype "bidirectional"))
    )
    (net (code "21") (name "5") (class "Default")
      (node (ref "B1") (pin "5") (pinfunction "5_5") (pintype "bidirectional"))
      (node (ref "DASH") (pin "2") (pinfunction "K_BLUE_2") (pintype "bidirectional"))
    )
    (net (code "22") (name "5V") (class "Default")
      (node (ref "B1") (pin "5V@0") (pinfunction "5V_5V@0") (pintype "bidirectional"))
      (node (ref "C1") (pin "2") (pinfunction "2_2") (pintype "passive"))
      (node (ref "C22") (pin "2") (pinfunction "2_2") (pintype "passive"))
      (node (ref "C23") (pin "1") (pinfunction "1_1") (pintype "passive"))
      (node (ref "C24") (pin "2") (pinfunction "2_2") (pintype "passive"))
      (node (ref "C25") (pin "1") (pinfunction "1_1") (pintype "passive"))
      (node (ref "C27") (pin "2") (pinfunction "2_2") (pintype "passive"))
      (node (ref "IC1") (pin "8") (pinfunction "VCC_8") (pintype "bidirectional"))
      (node (ref "J1") (pin "12") (pinfunction "12_12") (pintype "passive"))
      (node (ref "J1") (pin "15") (pinfunction "15_15") (pintype "passive"))
      (node (ref "J2") (pin "3") (pinfunction "3_3") (pintype "passive"))
      (node (ref "JP1") (pin "1") (pinfunction "1_1") (pintype "passive"))
      (node (ref "Q1") (pin "1") (pinfunction "G_1") (pintype "passive"))
      (node (ref "Q2") (pin "1") (pinfunction "G_1") (pintype "passive"))
      (node (ref "R1") (pin "2") (pinfunction "2_2") (pintype "passive"))
      (node (ref "R10") (pin "2") (pinfunction "2_2") (pintype "passive"))
      (node (ref "R11") (pin "2") (pinfunction "2_2") (pintype "passive"))
      (node (ref "R12") (pin "2") (pinfunction "2_2") (pintype "passive"))
      (node (ref "R13") (pin "2") (pinfunction "2_2") (pintype "passive"))
      (node (ref "R14") (pin "2") (pinfunction "2_2") (pintype "passive"))
      (node (ref "R15") (pin "2") (pinfunction "2_2") (pintype "passive"))
      (node (ref "R16") (pin "2") (pinfunction "2_2") (pintype "passive"))
      (node (ref "R17") (pin "2") (pinfunction "2_2") (pintype "passive"))
      (node (ref "R18") (pin "2") (pinfunction "2_2") (pintype "passive"))
      (node (ref "R19") (pin "2") (pinfunction "2_2") (pintype "passive"))
      (node (ref "R20") (pin "2") (pinfunction "2_2") (pintype "passive"))
      (node (ref "R21") (pin "2") (pinfunction "2_2") (pintype "passive"))
      (node (ref "R22") (pin "2") (pinfunction "2_2") (pintype "passive"))
      (node (ref "R23") (pin "2") (pinfunction "2_2") (pintype "passive"))
      (node (ref "R24") (pin "1") (pinfunction "1_1") (pintype "passive"))
      (node (ref "R3") (pin "2") (pinfunction "2_2") (pintype "passive"))
      (node (ref "R41") (pin "1") (pinfunction "1_1") (pintype "passive"))
      (node (ref "R42") (pin "1") (pinfunction "1_1") (pintype "passive"))
      (node (ref "R43") (pin "2") (pinfunction "2_2") (pintype "passive"))
      (node (ref "R44") (pin "1") (pinfunction "1_1") (pintype "passive"))
      (node (ref "R45") (pin "1") (pinfunction "1_1") (pintype "passive"))
      (node (ref "R46") (pin "2") (pinfunction "2_2") (pintype "passive"))
      (node (ref "R47") (pin "1") (pinfunction "1_1") (pintype "passive"))
      (node (ref "R48") (pin "1") (pinfunction "1_1") (pintype "passive"))
      (node (ref "R49") (pin "1") (pinfunction "1_1") (pintype "passive"))
      (node (ref "R5") (pin "1") (pinfunction "1_1") (pintype "passive"))
      (node (ref "R50") (pin "2") (pinfunction "2_2") (pintype "passive"))
      (node (ref "R60") (pin "1") (pinfunction "1_1") (pintype "passive"))
      (node (ref "R63") (pin "1") (pinfunction "1_1") (pintype "passive"))
      (node (ref "R66") (pin "1") (pinfunction "1_1") (pintype "passive"))
      (node (ref "R69") (pin "1") (pinfunction "1_1") (pintype "passive"))
      (node (ref "R9") (pin "1") (pinfunction "1_1") (pintype "passive"))
      (node (ref "SW1") (pin "1") (pinfunction "1_1") (pintype "passive"))
      (node (ref "SW2") (pin "1") (pinfunction "1_1") (pintype "passive"))
      (node (ref "U1") (pin "1") (pinfunction "VIN_1") (pintype "power_in"))
      (node (ref "U4") (pin "5V") (pinfunction "5V_5V") (pintype "bidirectional"))
      (node (ref "U6") (pin "12") (pinfunction "AVDD_12") (pintype "power_in"))
      (node (ref "U6") (pin "13") (pinfunction "DVDD_13") (pintype "power_in"))
      (node (ref "U6") (pin "3") (pinfunction "RESET_N_3") (pintype "input"))
      (node (ref "U7") (pin "12") (pinfunction "AVDD_12") (pintype "power_in"))
      (node (ref "U7") (pin "13") (pinfunction "DVDD_13") (pintype "power_in"))
      (node (ref "U7") (pin "3") (pinfunction "RESET_N_3") (pintype "input"))
    )
    (net (code "23") (name "5VOR0V") (class "Default")
      (node (ref "R61") (pin "1") (pinfunction "1_1") (pintype "passive"))
      (node (ref "R64") (pin "1") (pinfunction "1_1") (pintype "passive"))
      (node (ref "R67") (pin "1") (pinfunction "1_1") (pintype "passive"))
      (node (ref "R70") (pin "1") (pinfunction "1_1") (pintype "passive"))
      (node (ref "SW1") (pin "2") (pinfunction "2_2") (pintype "passive"))
    )
    (net (code "24") (name "6") (class "Default")
      (node (ref "B1") (pin "6") (pinfunction "6_6") (pintype "bidirectional"))
      (node (ref "DASH") (pin "3") (pinfunction "K_RED_3") (pintype "bidirectional"))
    )
    (net (code "25") (name "7") (class "Default")
      (node (ref "B1") (pin "7") (pinfunction "7_7") (pintype "bidirectional"))
      (node (ref "DASH") (pin "4") (pinfunction "K_GREEN_4") (pintype "bidirectional"))
    )
    (net (code "26") (name "8") (class "Default")
      (node (ref "B1") (pin "8") (pinfunction "8_8") (pintype "bidirectional"))
      (node (ref "LAMBDAS") (pin "2") (pinfunction "K_BLUE_2") (pintype "bidirectional"))
    )
    (net (code "27") (name "9") (class "Default")
      (node (ref "B1") (pin "9") (pinfunction "9_9") (pintype "bidirectional"))
      (node (ref "LAMBDAS") (pin "3") (pinfunction "K_RED_3") (pintype "bidirectional"))
    )
    (net (code "28") (name "10") (class "Default")
      (node (ref "B1") (pin "10") (pinfunction "10_10") (pintype "bidirectional"))
      (node (ref "LAMBDAS") (pin "4") (pinfunction "K_GREEN_4") (pintype "bidirectional"))
    )
    (net (code "29") (name "12V") (class "Default")
      (node (ref "B1") (pin "VIN") (pinfunction "VIN_VIN") (pintype "bidirectional"))
      (node (ref "C26") (pin "2") (pinfunction "2_2") (pintype "passive"))
      (node (ref "J1") (pin "26") (pinfunction "26_26") (pintype "passive"))
      (node (ref "J1") (pin "54") (pinfunction "54_54") (pintype "passive"))
      (node (ref "J2") (pin "1") (pinfunction "1_1") (pintype "passive"))
    )
    (net (code "30") (name "14") (class "Default")
      (node (ref "B1") (pin "14") (pinfunction "14(TX3)_14") (pintype "bidirectional"))
      (node (ref "BRAKETEMP") (pin "3") (pinfunction "K_RED_3") (pintype "bidirectional"))
    )
    (net (code "31") (name "15") (class "Default")
      (node (ref "B1") (pin "15") (pinfunction "15(RX3)_15") (pintype "bidirectional"))
      (node (ref "BRAKETEMP") (pin "2") (pinfunction "K_BLUE_2") (pintype "bidirectional"))
    )
    (net (code "32") (name "16") (class "Default")
      (node (ref "B1") (pin "16") (pinfunction "16(TX2)_16") (pintype "bidirectional"))
      (node (ref "SHOCKPOT") (pin "4") (pinfunction "K_GREEN_4") (pintype "bidirectional"))
    )
    (net (code "33") (name "17") (class "Default")
      (node (ref "B1") (pin "17") (pinfunction "17(RX2)_17") (pintype "bidirectional"))
      (node (ref "SHOCKPOT") (pin "3") (pinfunction "K_RED_3") (pintype "bidirectional"))
    )
    (net (code "34") (name "18") (class "Default")
      (node (ref "B1") (pin "18") (pinfunction "18(TX1)_18") (pintype "bidirectional"))
      (node (ref "SHOCKPOT") (pin "2") (pinfunction "K_BLUE_2") (pintype "bidirectional"))
    )
    (net (code "35") (name "19") (class "Default")
      (node (ref "B1") (pin "19") (pinfunction "19(RX1)_19") (pintype "bidirectional"))
      (node (ref "BRAKEPRES") (pin "4") (pinfunction "K_GREEN_4") (pintype "bidirectional"))
    )
    (net (code "36") (name "22") (class "Default")
      (node (ref "B1") (pin "22") (pinfunction "22_22") (pintype "bidirectional"))
      (node (ref "BRAKEPRES") (pin "3") (pinfunction "K_RED_3") (pintype "bidirectional"))
    )
    (net (code "37") (name "23") (class "Default")
      (node (ref "B1") (pin "23") (pinfunction "23_23") (pintype "bidirectional"))
      (node (ref "BRAKEPRES") (pin "2") (pinfunction "K_BLUE_2") (pintype "bidirectional"))
    )
    (net (code "38") (name "24") (class "Default")
      (node (ref "B1") (pin "24") (pinfunction "24_24") (pintype "bidirectional"))
      (node (ref "INTAKEPRES") (pin "4") (pinfunction "K_GREEN_4") (pintype "bidirectional"))
    )
    (net (code "39") (name "25") (class "Default")
      (node (ref "B1") (pin "25") (pinfunction "25_25") (pintype "bidirectional"))
      (node (ref "INTAKEPRES") (pin "3") (pinfunction "K_RED_3") (pintype "bidirectional"))
    )
    (net (code "40") (name "26") (class "Default")
      (node (ref "B1") (pin "26") (pinfunction "26_26") (pintype "bidirectional"))
      (node (ref "INTAKEPRES") (pin "2") (pinfunction "K_BLUE_2") (pintype "bidirectional"))
    )
    (net (code "41") (name "27") (class "Default")
      (node (ref "B1") (pin "27") (pinfunction "27_27") (pintype "bidirectional"))
      (node (ref "INTAKETEMP") (pin "4") (pinfunction "K_GREEN_4") (pintype "bidirectional"))
    )
    (net (code "42") (name "28") (class "Default")
      (node (ref "B1") (pin "28") (pinfunction "28_28") (pintype "bidirectional"))
      (node (ref "INTAKETEMP") (pin "3") (pinfunction "K_RED_3") (pintype "bidirectional"))
    )
    (net (code "43") (name "29") (class "Default")
      (node (ref "B1") (pin "29") (pinfunction "29_29") (pintype "bidirectional"))
      (node (ref "INTAKETEMP") (pin "2") (pinfunction "K_BLUE_2") (pintype "bidirectional"))
    )
    (net (code "44") (name "30") (class "Default")
      (node (ref "B1") (pin "30") (pinfunction "30_30") (pintype "bidirectional"))
      (node (ref "COOLANTTEMP") (pin "4") (pinfunction "K_GREEN_4") (pintype "bidirectional"))
    )
    (net (code "45") (name "31") (class "Default")
      (node (ref "B1") (pin "31") (pinfunction "31_31") (pintype "bidirectional"))
      (node (ref "COOLANTTEMP") (pin "3") (pinfunction "K_RED_3") (pintype "bidirectional"))
    )
    (net (code "46") (name "32") (class "Default")
      (node (ref "B1") (pin "32") (pinfunction "32_32") (pintype "bidirectional"))
      (node (ref "COOLANTTEMP") (pin "2") (pinfunction "K_BLUE_2") (pintype "bidirectional"))
    )
    (net (code "47") (name "33") (class "Default")
      (node (ref "B1") (pin "33") (pinfunction "33_33") (pintype "bidirectional"))
      (node (ref "OILPRES") (pin "4") (pinfunction "K_GREEN_4") (pintype "bidirectional"))
    )
    (net (code "48") (name "34") (class "Default")
      (node (ref "B1") (pin "34") (pinfunction "34_34") (pintype "bidirectional"))
      (node (ref "OILPRES") (pin "3") (pinfunction "K_RED_3") (pintype "bidirectional"))
    )
    (net (code "49") (name "35") (class "Default")
      (node (ref "B1") (pin "35") (pinfunction "35_35") (pintype "bidirectional"))
      (node (ref "OILPRES") (pin "2") (pinfunction "K_BLUE_2") (pintype "bidirectional"))
    )
    (net (code "50") (name "36") (class "Default")
      (node (ref "B1") (pin "36") (pinfunction "36_36") (pintype "bidirectional"))
      (node (ref "OILTEMP") (pin "4") (pinfunction "K_GREEN_4") (pintype "bidirectional"))
    )
    (net (code "51") (name "37") (class "Default")
      (node (ref "B1") (pin "37") (pinfunction "37_37") (pintype "bidirectional"))
      (node (ref "OILTEMP") (pin "3") (pinfunction "K_RED_3") (pintype "bidirectional"))
    )
    (net (code "52") (name "38") (class "Default")
      (node (ref "B1") (pin "38") (pinfunction "38_38") (pintype "bidirectional"))
      (node (ref "OILTEMP") (pin "2") (pinfunction "K_BLUE_2") (pintype "bidirectional"))
    )
    (net (code "53") (name "39") (class "Default")
      (node (ref "B1") (pin "39") (pinfunction "39_39") (pintype "bidirectional"))
      (node (ref "SPARE1") (pin "4") (pinfunction "K_GREEN_4") (pintype "bidirectional"))
    )
    (net (code "54") (name "40") (class "Default")
      (node (ref "B1") (pin "40") (pinfunction "40_40") (pintype "bidirectional"))
      (node (ref "SPARE1") (pin "3") (pinfunction "K_RED_3") (pintype "bidirectional"))
    )
    (net (code "55") (name "41") (class "Default")
      (node (ref "B1") (pin "41") (pinfunction "41_41") (pintype "bidirectional"))
      (node (ref "SPARE1") (pin "2") (pinfunction "K_BLUE_2") (pintype "bidirectional"))
    )
    (net (code "56") (name "42") (class "Default")
      (node (ref "B1") (pin "42") (pinfunction "42_42") (pintype "bidirectional"))
      (node (ref "SPARE2") (pin "4") (pinfunction "K_GREEN_4") (pintype "bidirectional"))
    )
    (net (code "57") (name "43") (class "Default")
      (node (ref "B1") (pin "43") (pinfunction "43_43") (pintype "bidirectional"))
      (node (ref "SPARE2") (pin "3") (pinfunction "K_RED_3") (pintype "bidirectional"))
    )
    (net (code "58") (name "44") (class "Default")
      (node (ref "B1") (pin "44") (pinfunction "44_44") (pintype "bidirectional"))
      (node (ref "SPARE2") (pin "2") (pinfunction "K_BLUE_2") (pintype "bidirectional"))
    )
    (net (code "59") (name "45") (class "Default")
      (node (ref "B1") (pin "45") (pinfunction "45_45") (pintype "bidirectional"))
      (node (ref "DAQ") (pin "4") (pinfunction "K_GREEN_4") (pintype "bidirectional"))
    )
    (net (code "60") (name "46") (class "Default")
      (node (ref "B1") (pin "46") (pinfunction "46_46") (pintype "bidirectional"))
      (node (ref "DAQ") (pin "3") (pinfunction "K_RED_3") (pintype "bidirectional"))
    )
    (net (code "61") (name "47") (class "Default")
      (node (ref "B1") (pin "47") (pinfunction "47_47") (pintype "bidirectional"))
      (node (ref "DAQ") (pin "2") (pinfunction "K_BLUE_2") (pintype "bidirectional"))
    )
    (net (code "62") (name "48") (class "Default")
      (node (ref "B1") (pin "48") (pinfunction "48_48") (pintype "bidirectional"))
      (node (ref "R71") (pin "1") (pinfunction "1_1") (pintype "passive"))
      (node (ref "SW2") (pin "2") (pinfunction "2_2") (pintype "passive"))
    )
    (net (code "63") (name "A0") (class "Default")
      (node (ref "B1") (pin "A0") (pinfunction "A0(RX0)_A0") (pintype "bidirectional"))
      (node (ref "C6") (pin "2") (pinfunction "2_2") (pintype "passive"))
      (node (ref "R25") (pin "2") (pinfunction "2_2") (pintype "passive"))
    )
    (net (code "64") (name "A0IN") (class "Default")
      (node (ref "J1") (pin "18") (pinfunction "18_18") (pintype "passive"))
      (node (ref "R25") (pin "1") (pinfunction "1_1") (pintype "passive"))
    )
    (net (code "65") (name "A1") (class "Default")
      (node (ref "B1") (pin "A1") (pinfunction "A1(TX0)_A1") (pintype "bidirectional"))
      (node (ref "C7") (pin "2") (pinfunction "2_2") (pintype "passive"))
      (node (ref "R26") (pin "2") (pinfunction "2_2") (pintype "passive"))
    )
    (net (code "66") (name "A1IN") (class "Default")
      (node (ref "J1") (pin "19") (pinfunction "19_19") (pintype "passive"))
      (node (ref "R26") (pin "1") (pinfunction "1_1") (pintype "passive"))
    )
    (net (code "67") (name "A2") (class "Default")
      (node (ref "B1") (pin "A2") (pinfunction "A2_A2") (pintype "bidirectional"))
      (node (ref "C8") (pin "2") (pinfunction "2_2") (pintype "passive"))
      (node (ref "R27") (pin "2") (pinfunction "2_2") (pintype "passive"))
    )
    (net (code "68") (name "A2IN") (class "Default")
      (node (ref "J1") (pin "20") (pinfunction "20_20") (pintype "passive"))
      (node (ref "R27") (pin "1") (pinfunction "1_1") (pintype "passive"))
    )
    (net (code "69") (name "A3") (class "Default")
      (node (ref "B1") (pin "A3") (pinfunction "A3_A3") (pintype "bidirectional"))
      (node (ref "C9") (pin "2") (pinfunction "2_2") (pintype "passive"))
      (node (ref "R28") (pin "2") (pinfunction "2_2") (pintype "passive"))
    )
    (net (code "70") (name "A3IN") (class "Default")
      (node (ref "J1") (pin "10") (pinfunction "10_10") (pintype "passive"))
      (node (ref "R28") (pin "1") (pinfunction "1_1") (pintype "passive"))
    )
    (net (code "71") (name "A4") (class "Default")
      (node (ref "B1") (pin "A4") (pinfunction "A4_A4") (pintype "bidirectional"))
      (node (ref "C10") (pin "2") (pinfunction "2_2") (pintype "passive"))
      (node (ref "R29") (pin "2") (pinfunction "2_2") (pintype "passive"))
    )
    (net (code "72") (name "A4IN") (class "Default")
      (node (ref "J1") (pin "1") (pinfunction "1_1") (pintype "passive"))
      (node (ref "R29") (pin "1") (pinfunction "1_1") (pintype "passive"))
    )
    (net (code "73") (name "A5") (class "Default")
      (node (ref "B1") (pin "A5") (pinfunction "A5_A5") (pintype "bidirectional"))
      (node (ref "C11") (pin "2") (pinfunction "2_2") (pintype "passive"))
      (node (ref "R30") (pin "2") (pinfunction "2_2") (pintype "passive"))
    )
    (net (code "74") (name "A5IN") (class "Default")
      (node (ref "J1") (pin "11") (pinfunction "11_11") (pintype "passive"))
      (node (ref "R30") (pin "1") (pinfunction "1_1") (pintype "passive"))
    )
    (net (code "75") (name "A6") (class "Default")
      (node (ref "B1") (pin "A6") (pinfunction "A6_A6") (pintype "bidirectional"))
      (node (ref "C12") (pin "2") (pinfunction "2_2") (pintype "passive"))
      (node (ref "R31") (pin "2") (pinfunction "2_2") (pintype "passive"))
    )
    (net (code "76") (name "A6IN") (class "Default")
      (node (ref "J1") (pin "9") (pinfunction "9_9") (pintype "passive"))
      (node (ref "R31") (pin "1") (pinfunction "1_1") (pintype "passive"))
    )
    (net (code "77") (name "A7") (class "Default")
      (node (ref "B1") (pin "A7") (pinfunction "A7_A7") (pintype "bidirectional"))
      (node (ref "C13") (pin "2") (pinfunction "2_2") (pintype "passive"))
      (node (ref "R32") (pin "2") (pinfunction "2_2") (pintype "passive"))
    )
    (net (code "78") (name "A7IN") (class "Default")
      (node (ref "J1") (pin "17") (pinfunction "17_17") (pintype "passive"))
      (node (ref "R32") (pin "1") (pinfunction "1_1") (pintype "passive"))
    )
    (net (code "79") (name "A8") (class "Default")
      (node (ref "B1") (pin "A8") (pinfunction "A8_A8") (pintype "bidirectional"))
      (node (ref "C14") (pin "2") (pinfunction "2_2") (pintype "passive"))
      (node (ref "R33") (pin "2") (pinfunction "2_2") (pintype "passive"))
    )
    (net (code "80") (name "A8IN") (class "Default")
      (node (ref "J1") (pin "8") (pinfunction "8_8") (pintype "passive"))
      (node (ref "R33") (pin "1") (pinfunction "1_1") (pintype "passive"))
    )
    (net (code "81") (name "A9") (class "Default")
      (node (ref "B1") (pin "A9") (pinfunction "A9_A9") (pintype "bidirectional"))
      (node (ref "C15") (pin "2") (pinfunction "2_2") (pintype "passive"))
      (node (ref "R34") (pin "2") (pinfunction "2_2") (pintype "passive"))
    )
    (net (code "82") (name "A9IN") (class "Default")
      (node (ref "J1") (pin "16") (pinfunction "16_16") (pintype "passive"))
      (node (ref "R34") (pin "1") (pinfunction "1_1") (pintype "passive"))
    )
    (net (code "83") (name "A10") (class "Default")
      (node (ref "B1") (pin "A10") (pinfunction "A10_A10") (pintype "bidirectional"))
      (node (ref "C16") (pin "2") (pinfunction "2_2") (pintype "passive"))
      (node (ref "R35") (pin "2") (pinfunction "2_2") (pintype "passive"))
    )
    (net (code "84") (name "A10IN") (class "Default")
      (node (ref "J1") (pin "7") (pinfunction "7_7") (pintype "passive"))
      (node (ref "R35") (pin "1") (pinfunction "1_1") (pintype "passive"))
    )
    (net (code "85") (name "A11") (class "Default")
      (node (ref "B1") (pin "A11") (pinfunction "A11_A11") (pintype "bidirectional"))
      (node (ref "C17") (pin "2") (pinfunction "2_2") (pintype "passive"))
      (node (ref "R36") (pin "2") (pinfunction "2_2") (pintype "passive"))
    )
    (net (code "86") (name "A11IN") (class "Default")
      (node (ref "J1") (pin "6") (pinfunction "6_6") (pintype "passive"))
      (node (ref "R36") (pin "1") (pinfunction "1_1") (pintype "passive"))
    )
    (net (code "87") (name "A12") (class "Default")
      (node (ref "B1") (pin "A12") (pinfunction "A12_A12") (pintype "bidirectional"))
      (node (ref "C18") (pin "2") (pinfunction "2_2") (pintype "passive"))
      (node (ref "R37") (pin "2") (pinfunction "2_2") (pintype "passive"))
    )
    (net (code "88") (name "A12IN") (class "Default")
      (node (ref "J1") (pin "13") (pinfunction "13_13") (pintype "passive"))
      (node (ref "R37") (pin "1") (pinfunction "1_1") (pintype "passive"))
    )
    (net (code "89") (name "A13") (class "Default")
      (node (ref "B1") (pin "A13") (pinfunction "A13_A13") (pintype "bidirectional"))
      (node (ref "C19") (pin "2") (pinfunction "2_2") (pintype "passive"))
      (node (ref "R38") (pin "2") (pinfunction "2_2") (pintype "passive"))
    )
    (net (code "90") (name "A13IN") (class "Default")
      (node (ref "J1") (pin "4") (pinfunction "4_4") (pintype "passive"))
      (node (ref "R38") (pin "1") (pinfunction "1_1") (pintype "passive"))
    )
    (net (code "91") (name "A14") (class "Default")
      (node (ref "B1") (pin "A14") (pinfunction "A14_A14") (pintype "bidirectional"))
      (node (ref "C20") (pin "2") (pinfunction "2_2") (pintype "passive"))
      (node (ref "R39") (pin "2") (pinfunction "2_2") (pintype "passive"))
    )
    (net (code "92") (name "A14IN") (class "Default")
      (node (ref "J1") (pin "5") (pinfunction "5_5") (pintype "passive"))
      (node (ref "R39") (pin "1") (pinfunction "1_1") (pintype "passive"))
    )
    (net (code "93") (name "A15") (class "Default")
      (node (ref "B1") (pin "A15") (pinfunction "A15_A15") (pintype "bidirectional"))
      (node (ref "C21") (pin "2") (pinfunction "2_2") (pintype "passive"))
      (node (ref "R40") (pin "2") (pinfunction "2_2") (pintype "passive"))
    )
    (net (code "94") (name "A15IN") (class "Default")
      (node (ref "J1") (pin "14") (pinfunction "14_14") (pintype "passive"))
      (node (ref "R40") (pin "1") (pinfunction "1_1") (pintype "passive"))
    )
    (net (code "95") (name "AREF") (class "Default")
      (node (ref "U4") (pin "AREF") (pinfunction "AREF_AREF") (pintype "bidirectional"))
    )
    (net (code "96") (name "CALIB") (class "Default")
      (node (ref "B1") (pin "13") (pinfunction "13_13") (pintype "bidirectional"))
      (node (ref "J1") (pin "31") (pinfunction "31_31") (pintype "passive"))
      (node (ref "R50") (pin "1") (pinfunction "1_1") (pintype "passive"))
    )
    (net (code "97") (name "CANHI") (class "Default")
      (node (ref "J1") (pin "60") (pinfunction "60_60") (pintype "passive"))
      (node (ref "JP1") (pin "3") (pinfunction "3_3") (pintype "passive"))
    )
    (net (code "98") (name "CANLO") (class "Default")
      (node (ref "J1") (pin "53") (pinfunction "53_53") (pintype "passive"))
      (node (ref "JP1") (pin "4") (pinfunction "4_4") (pintype "passive"))
    )
    (net (code "99") (name "CAN_CS") (class "Default")
      (node (ref "B1") (pin "49") (pinfunction "49_49") (pintype "bidirectional"))
      (node (ref "U4") (pin "D10") (pinfunction "*D10_D10") (pintype "bidirectional"))
    )
    (net (code "100") (name "CAN_INT") (class "Default")
      (node (ref "U4") (pin "D2") (pinfunction "D2_D2") (pintype "bidirectional"))
    )
    (net (code "101") (name "D3") (class "Default")
      (node (ref "U4") (pin "D3") (pinfunction "*D3_D3") (pintype "bidirectional"))
    )
    (net (code "102") (name "D4") (class "Default")
      (node (ref "U4") (pin "D4") (pinfunction "D4_D4") (pintype "bidirectional"))
    )
    (net (code "103") (name "D5") (class "Default")
      (node (ref "U4") (pin "D5") (pinfunction "*D5_D5") (pintype "bidirectional"))
    )
    (net (code "104") (name "DIN") (class "Default")
      (node (ref "Q1") (pin "2") (pinfunction "S_2") (pintype "passive"))
      (node (ref "R3") (pin "1") (pinfunction "1_1") (pintype "passive"))
      (node (ref "XB1") (pin "3") (pinfunction "DIN/~{CONFIG}_3") (pintype "input"))
    )
    (net (code "105") (name "DOUT") (class "Default")
      (node (ref "Q2") (pin "2") (pinfunction "S_2") (pintype "passive"))
      (node (ref "R1") (pin "1") (pinfunction "1_1") (pintype "passive"))
      (node (ref "XB1") (pin "2") (pinfunction "DOUT_2") (pintype "output"))
    )
    (net (code "106") (name "FL_WS") (class "Default")
      (node (ref "B1") (pin "2") (pinfunction "2_2") (pintype "bidirectional"))
      (node (ref "J1") (pin "25") (pinfunction "25_25") (pintype "passive"))
      (node (ref "R47") (pin "2") (pinfunction "2_2") (pintype "passive"))
    )
    (net (code "107") (name "FR_WS") (class "Default")
      (node (ref "B1") (pin "3") (pinfunction "3_3") (pintype "bidirectional"))
      (node (ref "J1") (pin "34") (pinfunction "34_34") (pintype "passive"))
      (node (ref "R48") (pin "2") (pinfunction "2_2") (pintype "passive"))
    )
    (net (code "108") (name "GND") (class "Default")
      (node (ref "B1") (pin "GND@0") (pinfunction "GND_GND@0") (pintype "bidirectional"))
      (node (ref "C1") (pin "1") (pinfunction "1_1") (pintype "passive"))
      (node (ref "C10") (pin "1") (pinfunction "1_1") (pintype "passive"))
      (node (ref "C11") (pin "1") (pinfunction "1_1") (pintype "passive"))
      (node (ref "C12") (pin "1") (pinfunction "1_1") (pintype "passive"))
      (node (ref "C13") (pin "1") (pinfunction "1_1") (pintype "passive"))
      (node (ref "C14") (pin "1") (pinfunction "1_1") (pintype "passive"))
      (node (ref "C15") (pin "1") (pinfunction "1_1") (pintype "passive"))
      (node (ref "C16") (pin "1") (pinfunction "1_1") (pintype "passive"))
      (node (ref "C17") (pin "1") (pinfunction "1_1") (pintype "passive"))
      (node (ref "C18") (pin "1") (pinfunction "1_1") (pintype "passive"))
      (node (ref "C19") (pin "1") (pinfunction "1_1") (pintype "passive"))
      (node (ref "C2") (pin "2") (pinfunction "2_2") (pintype "passive"))
      (node (ref "C20") (pin "1") (pinfunction "1_1") (pintype "passive"))
      (node (ref "C21") (pin "1") (pinfunction "1_1") (pintype "passive"))
      (node (ref "C22") (pin "1") (pinfunction "1_1") (pintype "passive"))
      (node (ref "C23") (pin "2") (pinfunction "2_2") (pintype "passive"))
      (node (ref "C24") (pin "1") (pinfunction "1_1") (pintype "passive"))
      (node (ref "C25") (pin "2") (pinfunction "2_2") (pintype "passive"))
      (node (ref "C26") (pin "1") (pinfunction "1_1") (pintype "passive"))
      (node (ref "C27") (pin "1") (pinfunction "1_1") (pintype "passive"))
      (node (ref "C28") (pin "1") (pinfunction "1_1") (pintype "passive"))
      (node (ref "C29") (pin "1") (pinfunction "1_1") (pintype "passive"))
      (node (ref "C3") (pin "1") (pinfunction "1_1") (pintype "passive"))
      (node (ref "C30") (pin "1") (pinfunction "1_1") (pintype "passive"))
      (node (ref "C31") (pin "1") (pinfunction "1_1") (pintype "passive"))
      (node (ref "C32") (pin "1") (pinfunction "1_1") (pintype "passive"))
      (node (ref "C33") (pin "1") (pinfunction "1_1") (pintype "passive"))
      (node (ref "C34") (pin "1") (pinfunction "1_1") (pintype "passive"))
      (node (ref "C35") (pin "1") (pinfunction "1_1") (pintype "passive"))
      (node (ref "C4") (pin "1") (pinfunction "1_1") (pintype "passive"))
      (node (ref "C5") (pin "1") (pinfunction "1_1") (pintype "passive"))
      (node (ref "C6") (pin "1") (pinfunction "1_1") (pintype "passive"))
      (node (ref "C7") (pin "1") (pinfunction "1_1") (pintype "passive"))
      (node (ref "C8") (pin "1") (pinfunction "1_1") (pintype "passive"))
      (node (ref "C9") (pin "1") (pinfunction "1_1") (pintype "passive"))
      (node (ref "IC1") (pin "4") (pinfunction "GND_4") (pintype "bidirectional"))
      (node (ref "J1") (pin "21") (pinfunction "21_21") (pintype "passive"))
      (node (ref "J1") (pin "22") (pinfunction "22_22") (pintype "passive"))
      (node (ref "J1") (pin "23") (pinfunction "23_23") (pintype "passive"))
      (node (ref "J1") (pin "24") (pinfunction "24_24") (pintype "passive"))
      (node (ref "J1") (pin "50") (pinfunction "50_50") (pintype "passive"))
      (node (ref "J1") (pin "51") (pinfunction "51_51") (pintype "passive"))
      (node (ref "J1") (pin "52") (pinfunction "52_52") (pintype "passive"))
      (node (ref "J2") (pin "2") (pinfunction "2_2") (pintype "passive"))
      (node (ref "JP1") (pin "2") (pinfunction "2_2") (pintype "passive"))
      (node (ref "R59") (pin "2") (pinfunction "2_2") (pintype "passive"))
      (node (ref "R6") (pin "1") (pinfunction "1_1") (pintype "passive"))
      (node (ref "R62") (pin "2") (pinfunction "2_2") (pintype "passive"))
      (node (ref "R65") (pin "2") (pinfunction "2_2") (pintype "passive"))
      (node (ref "R68") (pin "2") (pinfunction "2_2") (pintype "passive"))
      (node (ref "R71") (pin "2") (pinfunction "2_2") (pintype "passive"))
      (node (ref "U1") (pin "2") (pinfunction "VSS_2") (pintype "passive"))
      (node (ref "U4") (pin "GND@0") (pinfunction "GND_GND@0") (pintype "bidirectional"))
      (node (ref "U4") (pin "GND@1") (pinfunction "GND_GND@1") (pintype "bidirectional"))
      (node (ref "U4") (pin "GND@2") (pinfunction "GND_GND@2") (pintype "bidirectional"))
      (node (ref "U6") (pin "4") (pinfunction "DGND_4") (pintype "power_in"))
      (node (ref "U6") (pin "5") (pinfunction "AGND_5") (pintype "power_in"))
      (node (ref "U7") (pin "4") (pinfunction "DGND_4") (pintype "power_in"))
      (node (ref "U7") (pin "5") (pinfunction "AGND_5") (pintype "power_in"))
      (node (ref "XB1") (pin "10") (pinfunction "GND_10") (pintype "power_in"))
    )
    (net (code "109") (name "JOY-CLICK") (class "Default")
      (node (ref "U4") (pin "A4") (pinfunction "A4_A4") (pintype "bidirectional"))
    )
    (net (code "110") (name "JOY-DOWN") (class "Default")
      (node (ref "U4") (pin "A3") (pinfunction "A3_A3") (pintype "bidirectional"))
    )
    (net (code "111") (name "JOY-LEFT") (class "Default")
      (node (ref "U4") (pin "A2") (pinfunction "A2_A2") (pintype "bidirectional"))
    )
    (net (code "112") (name "JOY-RIGHT") (class "Default")
      (node (ref "U4") (pin "A5") (pinfunction "A5_A5") (pintype "bidirectional"))
    )
    (net (code "113") (name "JOY-UP") (class "Default")
      (node (ref "U4") (pin "A1") (pinfunction "A1_A1") (pintype "bidirectional"))
    )
    (net (code "114") (name "LCD") (class "Default")
      (node (ref "U4") (pin "D6") (pinfunction "*D6_D6") (pintype "bidirectional"))
    )
    (net (code "115") (name "LCL") (class "Default")
      (node (ref "IC1") (pin "7") (pinfunction "LY_7") (pintype "bidirectional"))
      (node (ref "J1") (pin "35") (pinfunction "35_35") (pintype "passive"))
      (node (ref "J1") (pin "36") (pinfunction "36_36") (pintype "passive"))
      (node (ref "J1") (pin "37") (pinfunction "37_37") (pintype "passive"))
      (node (ref "J1") (pin "38") (pinfunction "38_38") (pintype "passive"))
      (node (ref "J1") (pin "39") (pinfunction "39_39") (pintype "passive"))
      (node (ref "J1") (pin "40") (pinfunction "40_40") (pintype "passive"))
      (node (ref "J1") (pin "41") (pinfunction "41_41") (pintype "passive"))
      (node (ref "J1") (pin "42") (pinfunction "42_42") (pintype "passive"))
      (node (ref "J1") (pin "43") (pinfunction "43_43") (pintype "passive"))
      (node (ref "J1") (pin "44") (pinfunction "44_44") (pintype "passive"))
      (node (ref "J1") (pin "45") (pinfunction "45_45") (pintype "passive"))
      (node (ref "J1") (pin "46") (pinfunction "46_46") (pintype "passive"))
      (node (ref "J1") (pin "47") (pinfunction "47_47") (pintype "passive"))
      (node (ref "J1") (pin "48") (pinfunction "48_48") (pintype "passive"))
      (node (ref "J1") (pin "49") (pinfunction "49_49") (pintype "passive"))
      (node (ref "J1") (pin "57") (pinfunction "57_57") (pintype "passive"))
      (node (ref "R10") (pin "1") (pinfunction "1_1") (pintype "passive"))
    )
    (net (code "116") (name "LDA") (class "Default")
      (node (ref "IC1") (pin "2") (pinfunction "LX_2") (pintype "bidirectional"))
      (node (ref "J1") (pin "32") (pinfunction "32_32") (pintype "passive"))
      (node (ref "R9") (pin "2") (pinfunction "2_2") (pintype "passive"))
    )
    (net (code "117") (name "LED1") (class "Default")
      (node (ref "U4") (pin "D8") (pinfunction "D8_D8") (pintype "bidirectional"))
    )
    (net (code "118") (name "LED2") (class "Default")
      (node (ref "U4") (pin "D7") (pinfunction "D7_D7") (pintype "bidirectional"))
    )
    (net (code "119") (name "MISO") (class "Default")
      (node (ref "B1") (pin "50") (pinfunction "50_50") (pintype "bidirectional"))
      (node (ref "U4") (pin "D12") (pinfunction "D12_D12") (pintype "bidirectional"))
    )
    (net (code "120") (name "MOSI") (class "Default")
      (node (ref "B1") (pin "51") (pinfunction "51_51") (pintype "bidirectional"))
      (node (ref "U4") (pin "D11") (pinfunction "*D11_D11") (pintype "bidirectional"))
    )
    (net (code "121") (name "Net-(BRAKEPRES-COMMON_ANODE)") (class "Default")
      (node (ref "BRAKEPRES") (pin "1") (pinfunction "COMMON_ANODE_1") (pintype "bidirectional"))
      (node (ref "R15") (pin "1") (pinfunction "1_1") (pintype "passive"))
    )
    (net (code "122") (name "Net-(BRAKETEMP-COMMON_ANODE)") (class "Default")
      (node (ref "BRAKETEMP") (pin "1") (pinfunction "COMMON_ANODE_1") (pintype "bidirectional"))
      (node (ref "R13") (pin "1") (pinfunction "1_1") (pintype "passive"))
    )
    (net (code "123") (name "Net-(COOLANTTEMP-COMMON_ANODE)") (class "Default")
      (node (ref "COOLANTTEMP") (pin "1") (pinfunction "COMMON_ANODE_1") (pintype "bidirectional"))
      (node (ref "R18") (pin "1") (pinfunction "1_1") (pintype "passive"))
    )
    (net (code "124") (name "Net-(DAQ-COMMON_ANODE)") (class "Default")
      (node (ref "DAQ") (pin "1") (pinfunction "COMMON_ANODE_1") (pintype "bidirectional"))
      (node (ref "R23") (pin "1") (pinfunction "1_1") (pintype "passive"))
    )
    (net (code "125") (name "Net-(DASH-COMMON_ANODE)") (class "Default")
      (node (ref "DASH") (pin "1") (pinfunction "COMMON_ANODE_1") (pintype "bidirectional"))
      (node (ref "R11") (pin "1") (pinfunction "1_1") (pintype "passive"))
    )
    (net (code "126") (name "Net-(INTAKEPRES-COMMON_ANODE)") (class "Default")
      (node (ref "INTAKEPRES") (pin "1") (pinfunction "COMMON_ANODE_1") (pintype "bidirectional"))
      (node (ref "R16") (pin "1") (pinfunction "1_1") (pintype "passive"))
    )
    (net (code "127") (name "Net-(INTAKETEMP-COMMON_ANODE)") (class "Default")
      (node (ref "INTAKETEMP") (pin "1") (pinfunction "COMMON_ANODE_1") (pintype "bidirectional"))
      (node (ref "R17") (pin "1") (pinfunction "1_1") (pintype "passive"))
    )
    (net (code "128") (name "Net-(LAMBDAS-COMMON_ANODE)") (class "Default")
      (node (ref "LAMBDAS") (pin "1") (pinfunction "COMMON_ANODE_1") (pintype "bidirectional"))
      (node (ref "R12") (pin "1") (pinfunction "1_1") (pintype "passive"))
    )
    (net (code "129") (name "Net-(OILPRES-COMMON_ANODE)") (class "Default")
      (node (ref "OILPRES") (pin "1") (pinfunction "COMMON_ANODE_1") (pintype "bidirectional"))
      (node (ref "R19") (pin "1") (pinfunction "1_1") (pintype "passive"))
    )
    (net (code "130") (name "Net-(OILTEMP-COMMON_ANODE)") (class "Default")
      (node (ref "OILTEMP") (pin "1") (pinfunction "COMMON_ANODE_1") (pintype "bidirectional"))
      (node (ref "R20") (pin "1") (pinfunction "1_1") (pintype "passive"))
    )
    (net (code "131") (name "Net-(R24-Pad2)") (class "Default")
      (node (ref "R24") (pin "2") (pinfunction "2_2") (pintype "passive"))
      (node (ref "REC") (pin "2") (pinfunction "2_2") (pintype "passive"))
    )
    (net (code "132") (name "Net-(R51-Pad2)") (class "Default")
      (node (ref "R51") (pin "2") (pinfunction "2_2") (pintype "passive"))
      (node (ref "R59") (pin "1") (pinfunction "1_1") (pintype "passive"))
      (node (ref "R60") (pin "2") (pinfunction "2_2") (pintype "passive"))
    )
    (net (code "133") (name "Net-(R53-Pad2)") (class "Default")
      (node (ref "R53") (pin "2") (pinfunction "2_2") (pintype "passive"))
      (node (ref "R62") (pin "1") (pinfunction "1_1") (pintype "passive"))
      (node (ref "R63") (pin "2") (pinfunction "2_2") (pintype "passive"))
    )
    (net (code "134") (name "Net-(R55-Pad2)") (class "Default")
      (node (ref "R55") (pin "2") (pinfunction "2_2") (pintype "passive"))
      (node (ref "R65") (pin "1") (pinfunction "1_1") (pintype "passive"))
      (node (ref "R66") (pin "2") (pinfunction "2_2") (pintype "passive"))
    )
    (net (code "135") (name "Net-(R57-Pad2)") (class "Default")
      (node (ref "R57") (pin "2") (pinfunction "2_2") (pintype "passive"))
      (node (ref "R68") (pin "1") (pinfunction "1_1") (pintype "passive"))
      (node (ref "R69") (pin "2") (pinfunction "2_2") (pintype "passive"))
    )
    (net (code "136") (name "Net-(SHOCKPOT-COMMON_ANODE)") (class "Default")
      (node (ref "R14") (pin "1") (pinfunction "1_1") (pintype "passive"))
      (node (ref "SHOCKPOT") (pin "1") (pinfunction "COMMON_ANODE_1") (pintype "bidirectional"))
    )
    (net (code "137") (name "Net-(SPARE1-COMMON_ANODE)") (class "Default")
      (node (ref "R21") (pin "1") (pinfunction "1_1") (pintype "passive"))
      (node (ref "SPARE1") (pin "1") (pinfunction "COMMON_ANODE_1") (pintype "bidirectional"))
    )
    (net (code "138") (name "Net-(SPARE2-COMMON_ANODE)") (class "Default")
      (node (ref "R22") (pin "1") (pinfunction "1_1") (pintype "passive"))
      (node (ref "SPARE2") (pin "1") (pinfunction "COMMON_ANODE_1") (pintype "bidirectional"))
    )
    (net (code "139") (name "Net-(U1-CE)") (class "Default")
      (node (ref "R5") (pin "2") (pinfunction "2_2") (pintype "passive"))
      (node (ref "R6") (pin "2") (pinfunction "2_2") (pintype "passive"))
      (node (ref "U1") (pin "3") (pinfunction "CE_3") (pintype "passive"))
    )
    (net (code "140") (name "Net-(U6-DRDY_N)") (class "Default")
      (node (ref "R43") (pin "1") (pinfunction "1_1") (pintype "passive"))
      (node (ref "U6") (pin "14") (pinfunction "DRDY_N_14") (pintype "output"))
    )
    (net (code "141") (name "Net-(U6-REFN)") (class "Default")
      (node (ref "R42") (pin "2") (pinfunction "2_2") (pintype "passive"))
      (node (ref "U6") (pin "8") (pinfunction "REFN_8") (pintype "input"))
    )
    (net (code "142") (name "Net-(U6-REFP)") (class "Default")
      (node (ref "R41") (pin "2") (pinfunction "2_2") (pintype "passive"))
      (node (ref "U6") (pin "9") (pinfunction "REFP_9") (pintype "input"))
    )
    (net (code "143") (name "Net-(U7-DRDY_N)") (class "Default")
      (node (ref "R46") (pin "1") (pinfunction "1_1") (pintype "passive"))
      (node (ref "U7") (pin "14") (pinfunction "DRDY_N_14") (pintype "output"))
    )
    (net (code "144") (name "Net-(U7-REFN)") (class "Default")
      (node (ref "R45") (pin "2") (pinfunction "2_2") (pintype "passive"))
      (node (ref "U7") (pin "8") (pinfunction "REFN_8") (pintype "input"))
    )
    (net (code "145") (name "Net-(U7-REFP)") (class "Default")
      (node (ref "R44") (pin "2") (pinfunction "2_2") (pintype "passive"))
      (node (ref "U7") (pin "9") (pinfunction "REFP_9") (pintype "input"))
    )
    (net (code "146") (name "Net-(XB1-~{DTR}{slash}SLEEP_RQ{slash}DI8)") (class "Default")
      (node (ref "R8") (pin "2") (pinfunction "2_2") (pintype "passive"))
      (node (ref "XB1") (pin "9") (pinfunction "~{DTR}/SLEEP_RQ/DI8_9") (pintype "bidirectional"))
    )
    (net (code "147") (name "Net-(XB1-~{RTS}{slash}AD6{slash}DIO6)") (class "Default")
      (node (ref "R7") (pin "2") (pinfunction "2_2") (pintype "passive"))
      (node (ref "XB1") (pin "16") (pinfunction "~{RTS}/AD6/DIO6_16") (pintype "bidirectional"))
    )
    (net (code "148") (name "REC") (class "Default")
      (node (ref "B1") (pin "11") (pinfunction "11_11") (pintype "bidirectional"))
      (node (ref "J1") (pin "33") (pinfunction "33_33") (pintype "passive"))
      (node (ref "R49") (pin "2") (pinfunction "2_2") (pintype "passive"))
      (node (ref "REC") (pin "1") (pinfunction "1_1") (pintype "passive"))
    )
    (net (code "149") (name "RS") (class "Default")
      (node (ref "U4") (pin "RES") (pinfunction "RES_RES") (pintype "bidirectional"))
    )
    (net (code "150") (name "RX") (class "Default")
      (node (ref "U4") (pin "RX") (pinfunction "RX_RX") (pintype "bidirectional"))
    )
    (net (code "151") (name "RX0") (class "Default")
      (node (ref "B1") (pin "0") (pinfunction "0(RX0)_0") (pintype "bidirectional"))
      (node (ref "Q2") (pin "3") (pinfunction "D_3") (pintype "passive"))
      (node (ref "R2") (pin "1") (pinfunction "1_1") (pintype "passive"))
    )
    (net (code "152") (name "SCK") (class "Default")
      (node (ref "B1") (pin "52") (pinfunction "52_52") (pintype "bidirectional"))
      (node (ref "U4") (pin "D13") (pinfunction "D13_D13") (pintype "bidirectional"))
    )
    (net (code "153") (name "SCL") (class "Default")
      (node (ref "B1") (pin "21") (pinfunction "21(SCL)_21") (pintype "bidirectional"))
      (node (ref "IC1") (pin "6") (pinfunction "SY_6") (pintype "bidirectional"))
      (node (ref "U6") (pin "16") (pinfunction "SCL_16") (pintype "input"))
      (node (ref "U6") (pin "2") (pinfunction "A1_2") (pintype "input"))
      (node (ref "U7") (pin "1") (pinfunction "A0_1") (pintype "input"))
      (node (ref "U7") (pin "16") (pinfunction "SCL_16") (pintype "input"))
    )
    (net (code "154") (name "SDA") (class "Default")
      (node (ref "B1") (pin "20") (pinfunction "20(SDA)_20") (pintype "bidirectional"))
      (node (ref "IC1") (pin "3") (pinfunction "SX_3") (pintype "bidirectional"))
      (node (ref "U6") (pin "1") (pinfunction "A0_1") (pintype "input"))
      (node (ref "U6") (pin "15") (pinfunction "SDA_15") (pintype "bidirectional"))
      (node (ref "U7") (pin "15") (pinfunction "SDA_15") (pintype "bidirectional"))
      (node (ref "U7") (pin "2") (pinfunction "A1_2") (pintype "input"))
    )
    (net (code "155") (name "SD_CS") (class "Default")
      (node (ref "B1") (pin "53") (pinfunction "53_53") (pintype "bidirectional"))
      (node (ref "U4") (pin "D9") (pinfunction "*D9_D9") (pintype "bidirectional"))
    )
    (net (code "156") (name "SG_11") (class "Default")
      (node (ref "J1") (pin "30") (pinfunction "30_30") (pintype "passive"))
      (node (ref "R58") (pin "2") (pinfunction "2_2") (pintype "passive"))
      (node (ref "R70") (pin "2") (pinfunction "2_2") (pintype "passive"))
    )
    (net (code "157") (name "SG_21") (class "Default")
      (node (ref "J1") (pin "29") (pinfunction "29_29") (pintype "passive"))
      (node (ref "R56") (pin "2") (pinfunction "2_2") (pintype "passive"))
      (node (ref "R67") (pin "2") (pinfunction "2_2") (pintype "passive"))
    )
    (net (code "158") (name "SG_31") (class "Default")
      (node (ref "J1") (pin "28") (pinfunction "28_28") (pintype "passive"))
      (node (ref "R54") (pin "2") (pinfunction "2_2") (pintype "passive"))
      (node (ref "R64") (pin "2") (pinfunction "2_2") (pintype "passive"))
    )
    (net (code "159") (name "SG_41") (class "Default")
      (node (ref "J1") (pin "27") (pinfunction "27_27") (pintype "passive"))
      (node (ref "R52") (pin "2") (pinfunction "2_2") (pintype "passive"))
      (node (ref "R61") (pin "2") (pinfunction "2_2") (pintype "passive"))
    )
    (net (code "160") (name "TX") (class "Default")
      (node (ref "U4") (pin "TX") (pinfunction "TX_TX") (pintype "bidirectional"))
    )
    (net (code "161") (name "TX0") (class "Default")
      (node (ref "B1") (pin "1") (pinfunction "1(TX0)_1") (pintype "bidirectional"))
      (node (ref "Q1") (pin "3") (pinfunction "D_3") (pintype "passive"))
      (node (ref "R4") (pin "1") (pinfunction "1_1") (pintype "passive"))
    )
    (net (code "162") (name "unconnected-(B1-5V-Pad5V@1)") (class "Default")
      (node (ref "B1") (pin "5V@1") (pinfunction "5V_5V@1") (pintype "bidirectional"))
    )
    (net (code "163") (name "unconnected-(B1-5V-Pad5V@2)") (class "Default")
      (node (ref "B1") (pin "5V@2") (pinfunction "5V_5V@2") (pintype "bidirectional"))
    )
    (net (code "164") (name "unconnected-(B1-GND-PadGND@1)") (class "Default")
      (node (ref "B1") (pin "GND@1") (pinfunction "GND_GND@1") (pintype "bidirectional"))
    )
    (net (code "165") (name "unconnected-(B1-GND-PadGND@2)") (class "Default")
      (node (ref "B1") (pin "GND@2") (pinfunction "GND_GND@2") (pintype "bidirectional"))
    )
    (net (code "166") (name "unconnected-(B1-GND-PadGND@3)") (class "Default")
      (node (ref "B1") (pin "GND@3") (pinfunction "GND_GND@3") (pintype "bidirectional"))
    )
    (net (code "167") (name "unconnected-(B1-GND-PadGND@4)") (class "Default")
      (node (ref "B1") (pin "GND@4") (pinfunction "GND_GND@4") (pintype "bidirectional"))
    )
    (net (code "168") (name "unconnected-(B1-Pad3.3V)") (class "Default")
      (node (ref "B1") (pin "3.3V") (pinfunction "3.3V_3.3V") (pintype "bidirectional"))
    )
    (net (code "169") (name "unconnected-(B1-Pad12)") (class "Default")
      (node (ref "B1") (pin "12") (pinfunction "12_12") (pintype "bidirectional"))
    )
    (net (code "170") (name "unconnected-(B1-PadAREF)") (class "Default")
      (node (ref "B1") (pin "AREF") (pinfunction "AREF_AREF") (pintype "bidirectional"))
    )
    (net (code "171") (name "unconnected-(B1-PadRESET)") (class "Default")
      (node (ref "B1") (pin "RESET") (pinfunction "RESET_RESET") (pintype "bidirectional"))
    )
    (net (code "172") (name "unconnected-(IC1-NC_1-Pad1)") (class "Default")
      (node (ref "IC1") (pin "1") (pinfunction "NC_1_1") (pintype "bidirectional"))
    )
    (net (code "173") (name "unconnected-(IC1-NC_2-Pad5)") (class "Default")
      (node (ref "IC1") (pin "5") (pinfunction "NC_2_5") (pintype "bidirectional"))
    )
    (net (code "174") (name "unconnected-(J1-Pad2)") (class "Default")
      (node (ref "J1") (pin "2") (pinfunction "2_2") (pintype "passive"))
    )
    (net (code "175") (name "unconnected-(J1-Pad3)") (class "Default")
      (node (ref "J1") (pin "3") (pinfunction "3_3") (pintype "passive"))
    )
    (net (code "176") (name "unconnected-(J1-Pad55)") (class "Default")
      (node (ref "J1") (pin "55") (pinfunction "55_55") (pintype "passive"))
    )
    (net (code "177") (name "unconnected-(J1-Pad56)") (class "Default")
      (node (ref "J1") (pin "56") (pinfunction "56_56") (pintype "passive"))
    )
    (net (code "178") (name "unconnected-(J1-Pad58)") (class "Default")
      (node (ref "J1") (pin "58") (pinfunction "58_58") (pintype "passive"))
    )
    (net (code "179") (name "unconnected-(J1-Pad59)") (class "Default")
      (node (ref "J1") (pin "59") (pinfunction "59_59") (pintype "passive"))
    )
    (net (code "180") (name "unconnected-(U1-NC-Pad4)") (class "Default")
      (node (ref "U1") (pin "4") (pinfunction "NC_4") (pintype "no_connect"))
    )
    (net (code "181") (name "unconnected-(U4-Pad3.3V)") (class "Default")
      (node (ref "U4") (pin "3.3V") (pinfunction "3.3V_3.3V") (pintype "bidirectional"))
    )
    (net (code "182") (name "unconnected-(U4-PadA0)") (class "Default")
      (node (ref "U4") (pin "A0") (pinfunction "A0_A0") (pintype "bidirectional"))
    )
    (net (code "183") (name "unconnected-(U4-PadIOREF)") (class "Default")
      (node (ref "U4") (pin "IOREF") (pinfunction "IOREF_IOREF") (pintype "bidirectional"))
    )
    (net (code "184") (name "unconnected-(U4-PadSCL)") (class "Default")
      (node (ref "U4") (pin "SCL") (pinfunction "SCL_SCL") (pintype "bidirectional"))
    )
    (net (code "185") (name "unconnected-(U4-PadSDA)") (class "Default")
      (node (ref "U4") (pin "SDA") (pinfunction "SDA_SDA") (pintype "bidirectional"))
    )
    (net (code "186") (name "unconnected-(U4-PadVIN)") (class "Default")
      (node (ref "U4") (pin "VIN") (pinfunction "VIN_VIN") (pintype "bidirectional"))
    )
    (net (code "187") (name "unconnected-(XB1-AD0{slash}DIO0-Pad20)") (class "Default")
      (node (ref "XB1") (pin "20") (pinfunction "AD0/DIO0_20") (pintype "bidirectional"))
    )
    (net (code "188") (name "unconnected-(XB1-AD1{slash}DIO1-Pad19)") (class "Default")
      (node (ref "XB1") (pin "19") (pinfunction "AD1/DIO1_19") (pintype "bidirectional"))
    )
    (net (code "189") (name "unconnected-(XB1-AD2{slash}DIO2-Pad18)") (class "Default")
      (node (ref "XB1") (pin "18") (pinfunction "AD2/DIO2_18") (pintype "bidirectional"))
    )
    (net (code "190") (name "unconnected-(XB1-ASSOC{slash}AD5{slash}DIO5-Pad15)") (class "Default")
      (node (ref "XB1") (pin "15") (pinfunction "ASSOC/AD5/DIO5_15") (pintype "bidirectional"))
    )
    (net (code "191") (name "unconnected-(XB1-CD{slash}DOUT_EN{slash}DO8-Pad4)") (class "Default")
      (node (ref "XB1") (pin "4") (pinfunction "CD/DOUT_EN/DO8_4") (pintype "output"))
    )
    (net (code "192") (name "unconnected-(XB1-COORD_SEL{slash}AD3{slash}DIO3-Pad17)") (class "Default")
      (node (ref "XB1") (pin "17") (pinfunction "COORD_SEL/AD3/DIO3_17") (pintype "bidirectional"))
    )
    (net (code "193") (name "unconnected-(XB1-ON{slash}~{SLEEP}-Pad13)") (class "Default")
      (node (ref "XB1") (pin "13") (pinfunction "ON/~{SLEEP}_13") (pintype "output"))
    )
    (net (code "194") (name "unconnected-(XB1-PWM0{slash}RSSI-Pad6)") (class "Default")
      (node (ref "XB1") (pin "6") (pinfunction "PWM0/RSSI_6") (pintype "output"))
    )
    (net (code "195") (name "unconnected-(XB1-RF_TX{slash}AD4{slash}DIO4-Pad11)") (class "Default")
      (node (ref "XB1") (pin "11") (pinfunction "RF_TX/AD4/DIO4_11") (pintype "bidirectional"))
    )
    (net (code "196") (name "unconnected-(XB1-VREF-Pad14)") (class "Default")
      (node (ref "XB1") (pin "14") (pinfunction "VREF_14") (pintype "input"))
    )
    (net (code "197") (name "unconnected-(XB1-~{CTS}{slash}DIO7-Pad12)") (class "Default")
      (node (ref "XB1") (pin "12") (pinfunction "~{CTS}/DIO7_12") (pintype "bidirectional"))
    )
    (net (code "198") (name "unconnected-(XB1-~{RESET}-Pad5)") (class "Default")
      (node (ref "XB1") (pin "5") (pinfunction "~{RESET}_5") (pintype "input"))
    )
  )
)
